# CHIP_PRO-Dev-Kit-v1_0.net
KiCad netlist of a schematic drawn in EAGLE
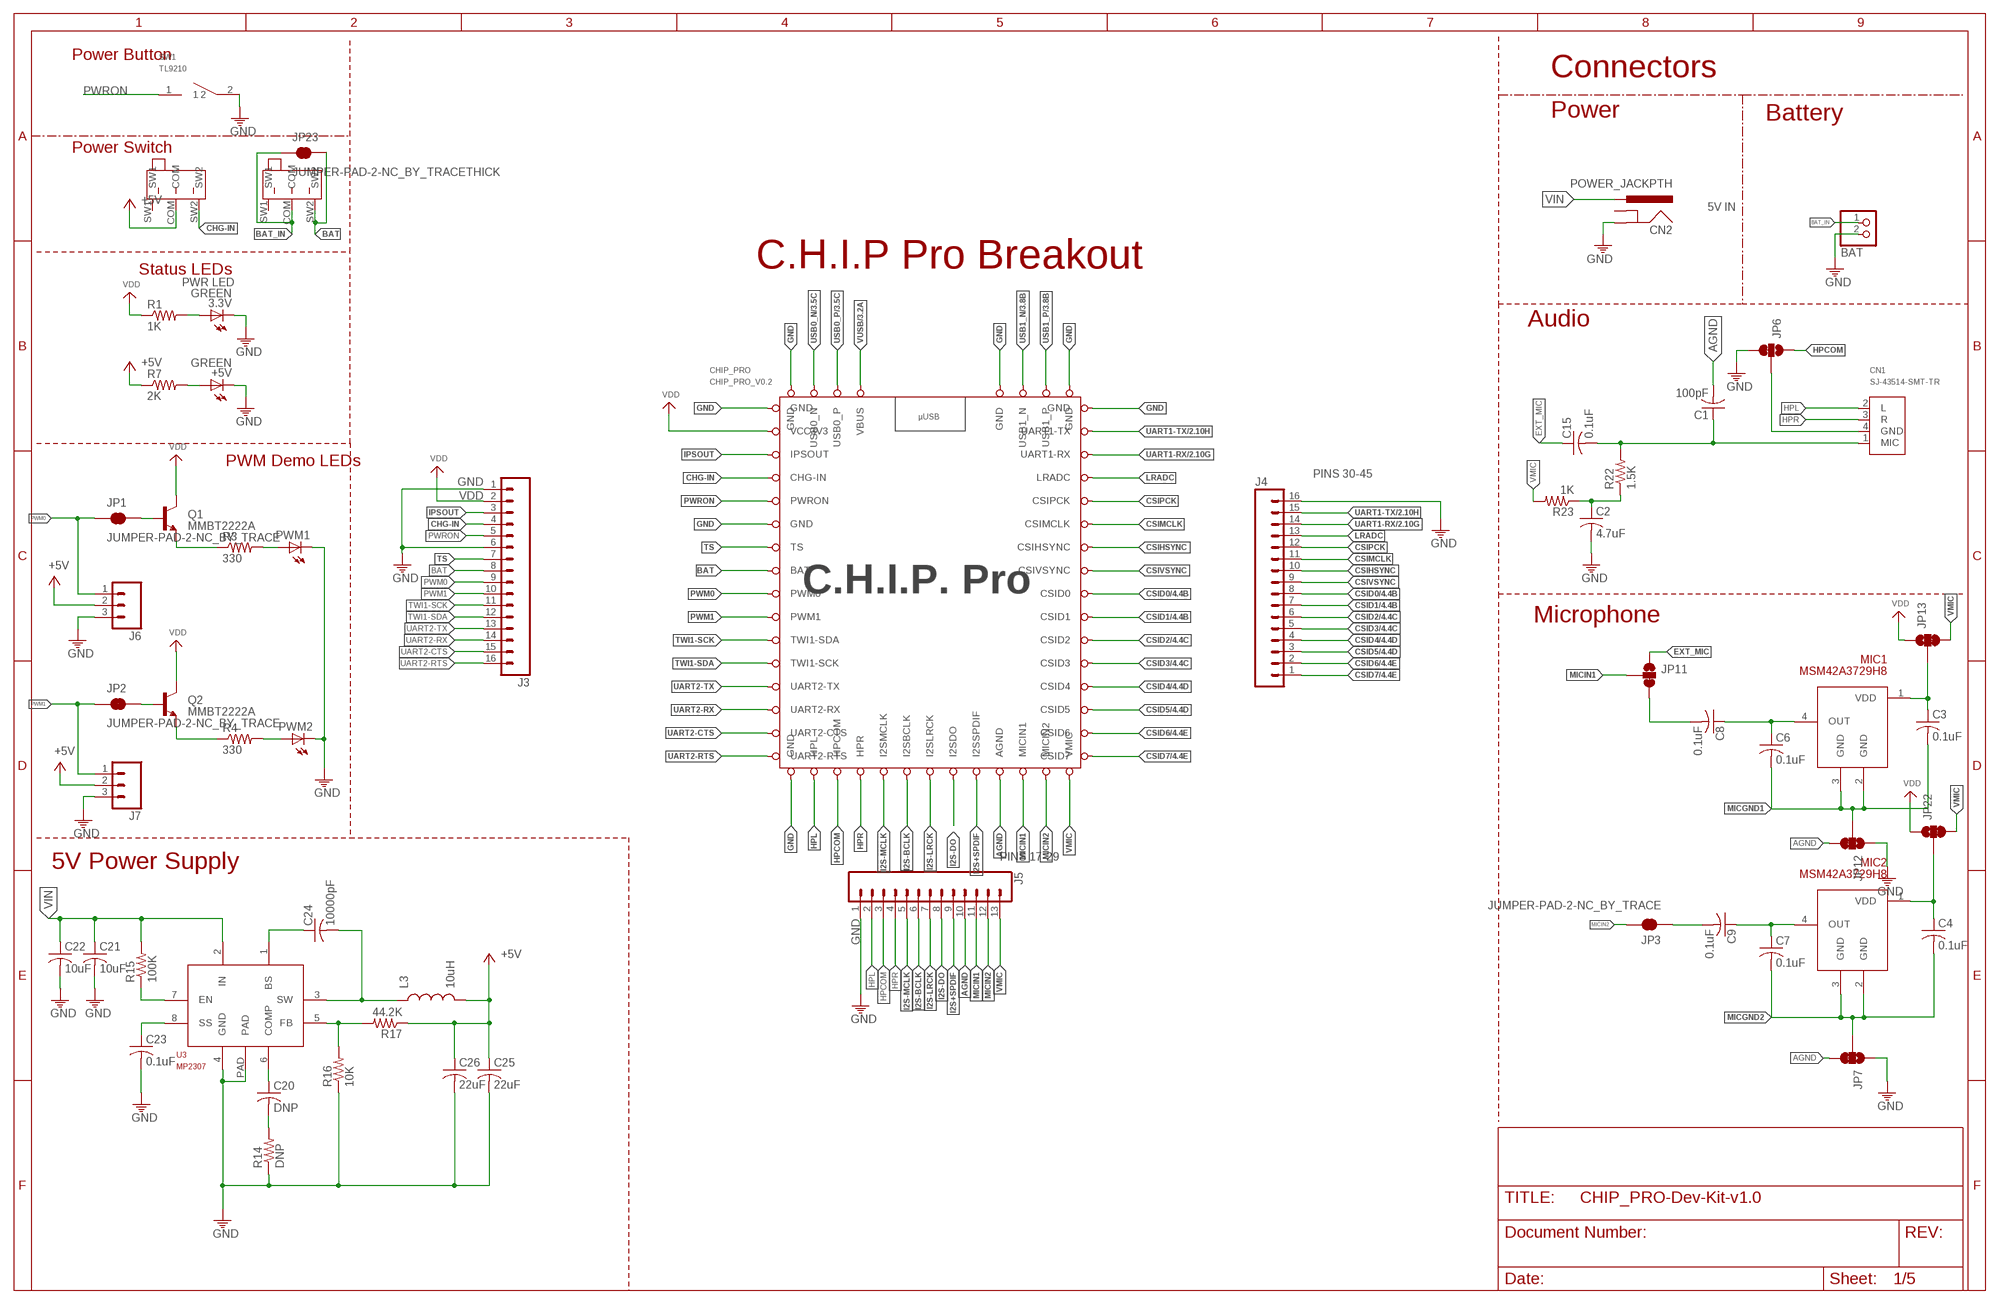
[diagram p0: schematic, sheet 1]
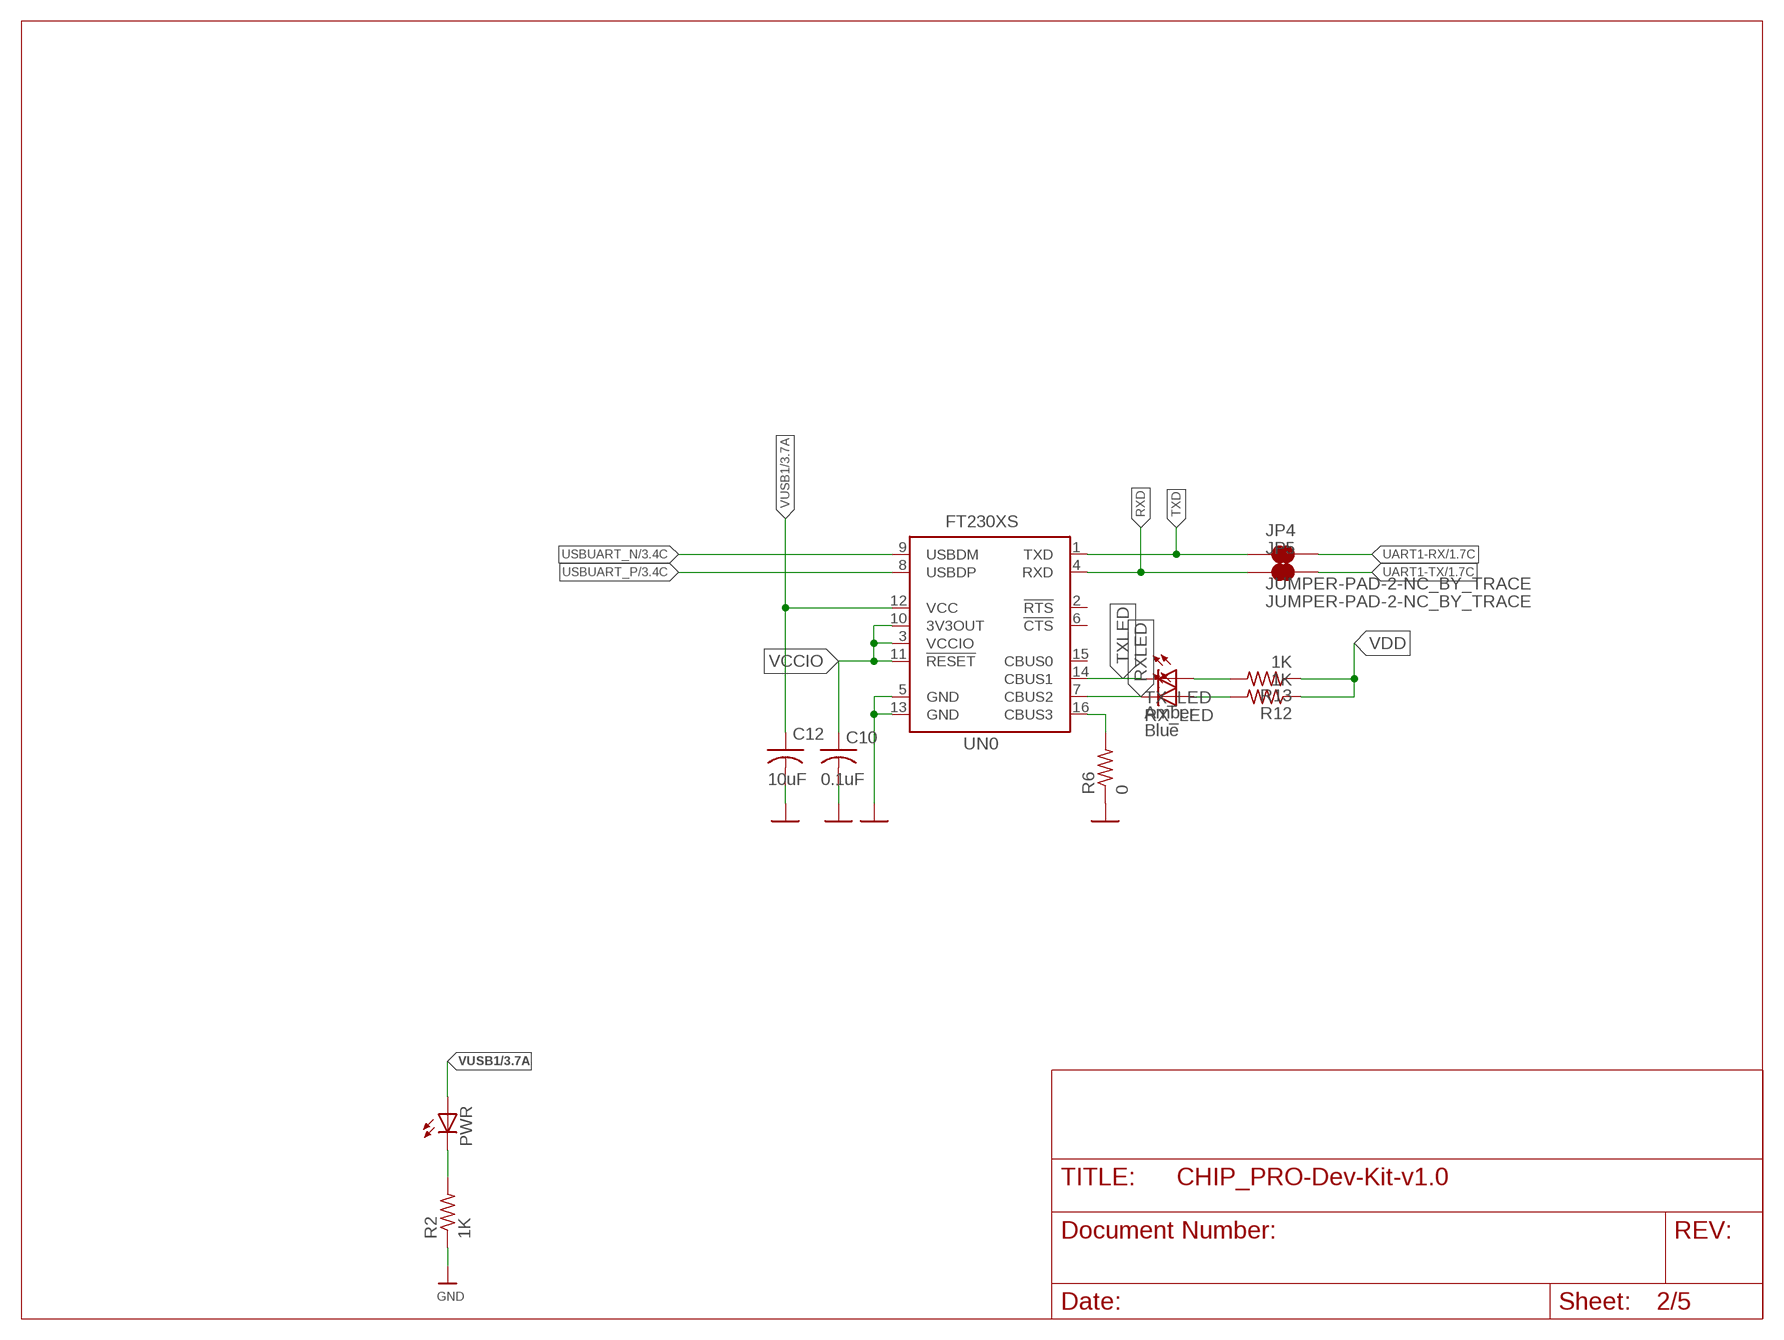
[diagram p1: schematic, sheet 2]
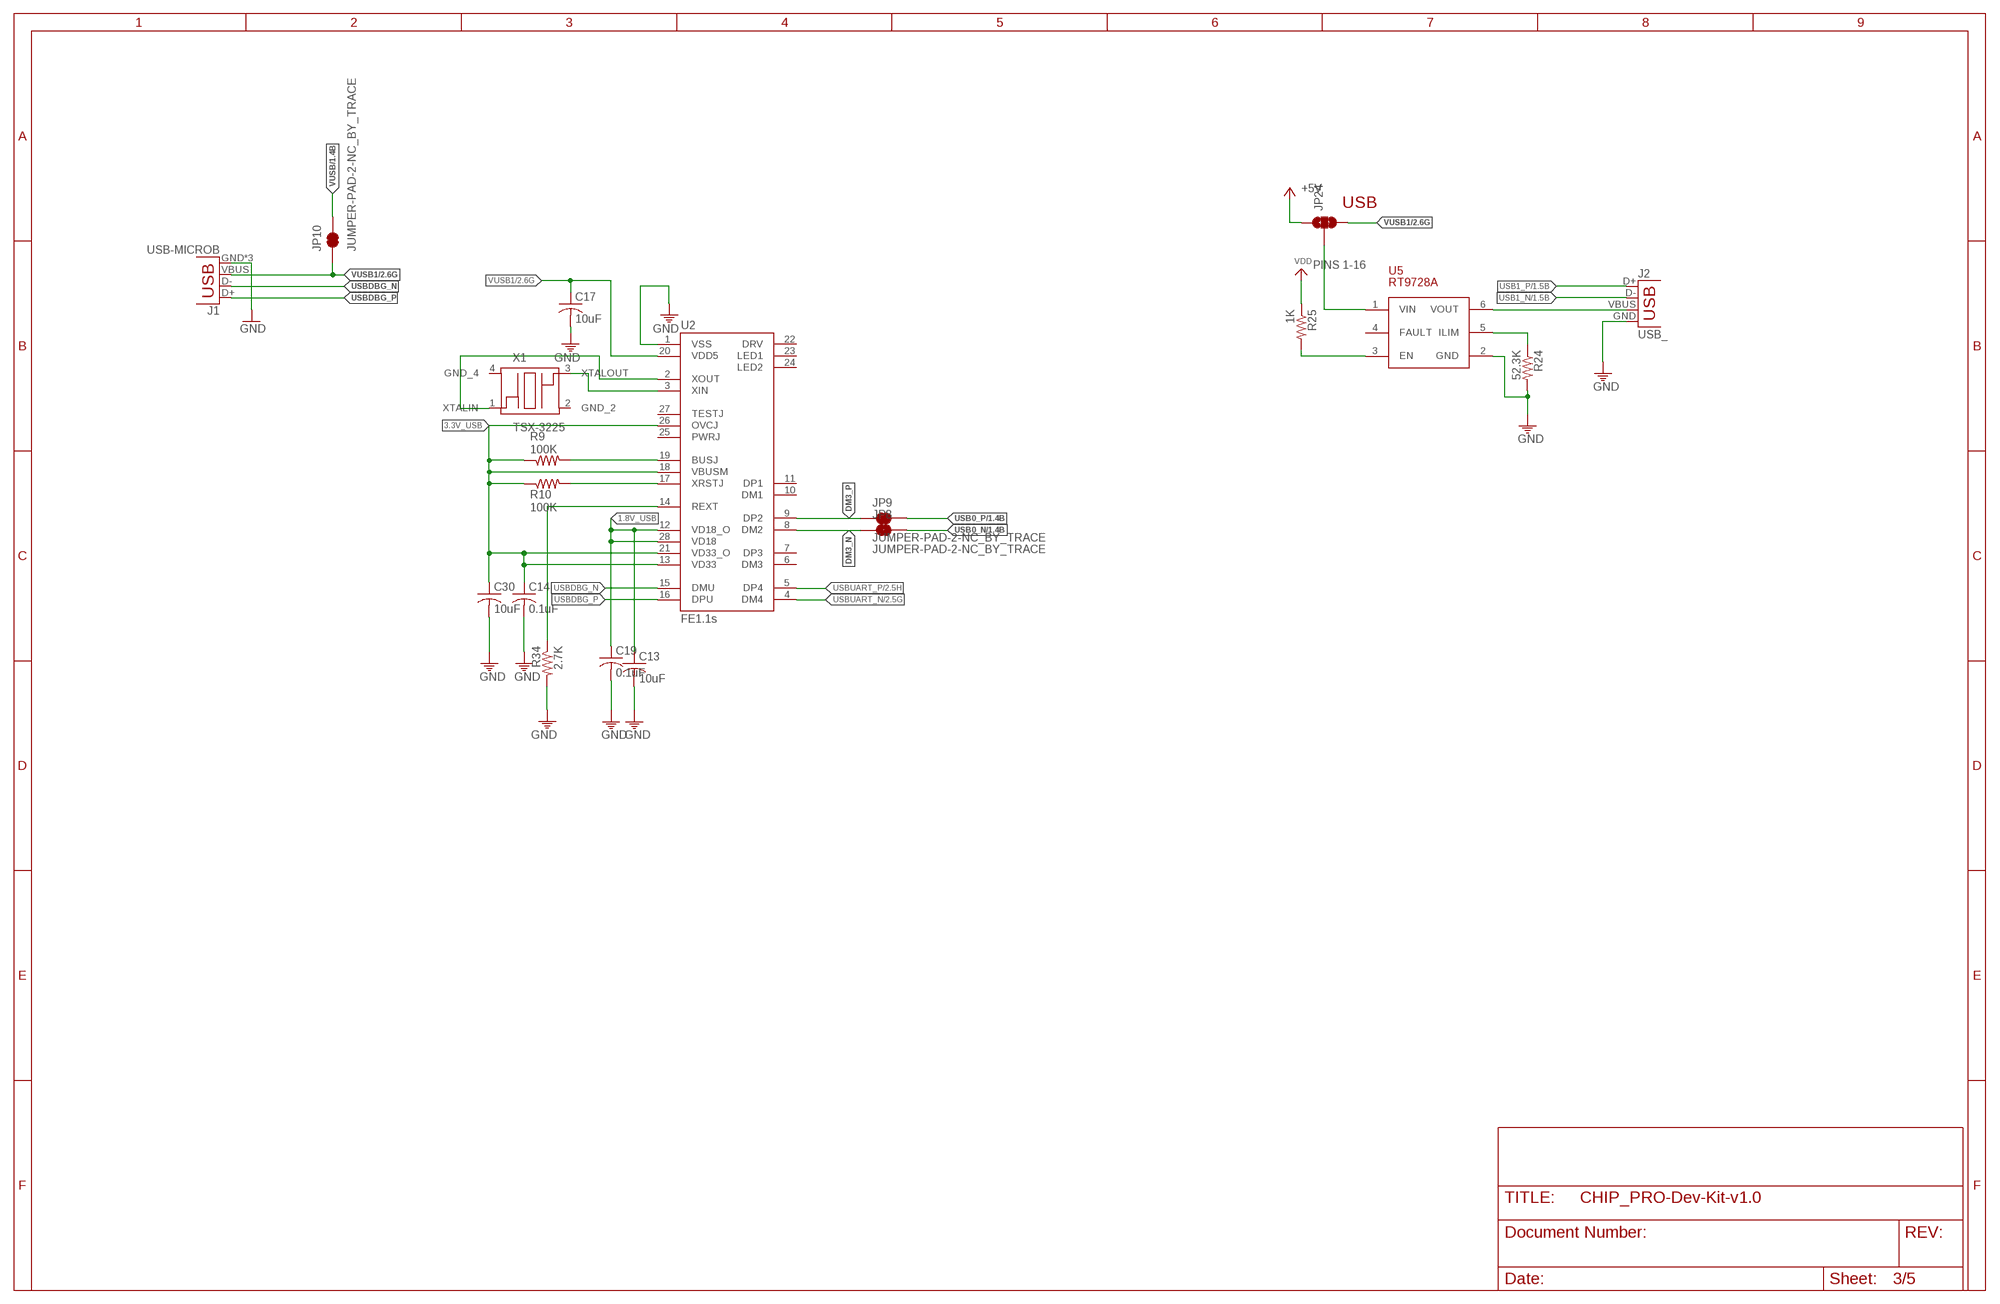
[diagram p2: schematic, sheet 3]
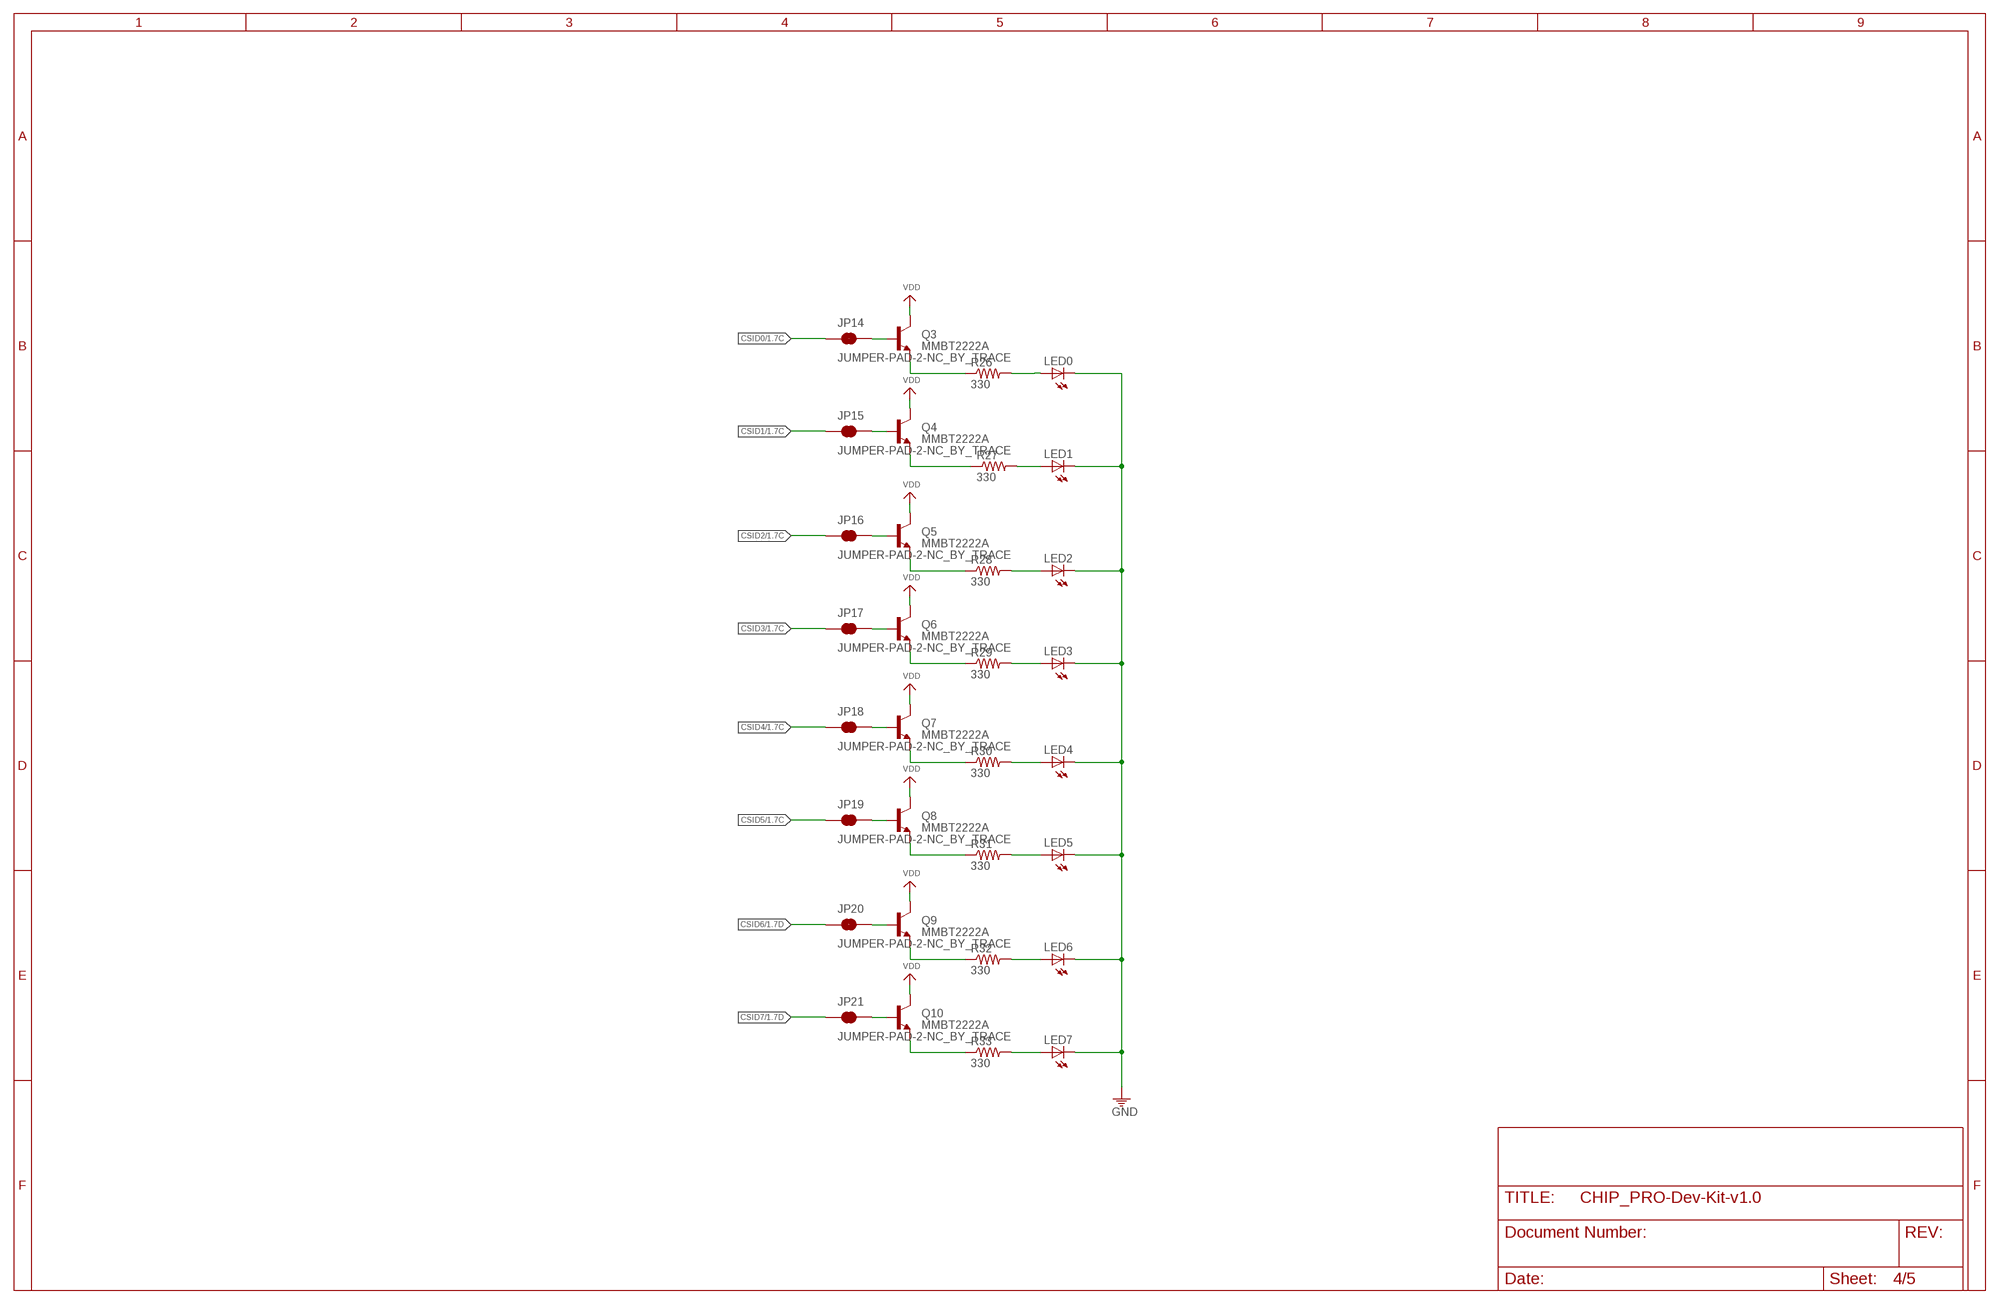
[diagram p3: schematic, sheet 4]

(export (version "E")
  (design (tool "Eeschema 10.0.6"))
  (components
    (comp (ref "C10")
      (value "0.1uF")
      (footprint "eagle-import:C0402")
      (libsource (lib "eagle-import") (part "C-USC0402"))
    )
    (comp (ref "C12")
      (value "10uF")
      (footprint "eagle-import:C0402")
      (libsource (lib "eagle-import") (part "C-USC0402"))
    )
    (comp (ref "JP4")
      (value "JUMPER-PAD-2-NC_BY_TRACE")
      (footprint "eagle-import:PAD-JUMPER-2-NC_BY_TRACE_YES_SILK")
      (libsource (lib "eagle-import") (part "JUMPER-PAD-2-NC_BY_TRACE"))
    )
    (comp (ref "JP5")
      (value "JUMPER-PAD-2-NC_BY_TRACE")
      (footprint "eagle-import:PAD-JUMPER-2-NC_BY_TRACE_YES_SILK")
      (libsource (lib "eagle-import") (part "JUMPER-PAD-2-NC_BY_TRACE"))
    )
    (comp (ref "PWR")
      (value "LED805")
      (footprint "eagle-import:LED-805")
      (libsource (lib "eagle-import") (part "LED805"))
    )
    (comp (ref "R2")
      (value "1K")
      (footprint "eagle-import:R0402")
      (libsource (lib "eagle-import") (part "GR8_Module-Eval-v0.1_R-US_R0402"))
    )
    (comp (ref "R6")
      (value "0")
      (footprint "eagle-import:R0402")
      (libsource (lib "eagle-import") (part "R-US_R0402"))
    )
    (comp (ref "R12")
      (value "1K")
      (footprint "eagle-import:R0402")
      (libsource (lib "eagle-import") (part "GR8_Module-Eval-v0.1_R-US_R0402"))
    )
    (comp (ref "R13")
      (value "1K")
      (footprint "eagle-import:R0402")
      (libsource (lib "eagle-import") (part "GR8_Module-Eval-v0.1_R-US_R0402"))
    )
    (comp (ref "RX_LED")
      (value "Blue")
      (footprint "eagle-import:LED-805")
      (libsource (lib "eagle-import") (part "LED805"))
    )
    (comp (ref "TX_LED")
      (value "Amber")
      (footprint "eagle-import:LED-805")
      (libsource (lib "eagle-import") (part "LED805"))
    )
    (comp (ref "UN0")
      (value "FT230XS")
      (footprint "eagle-import:SSOP-16")
      (libsource (lib "eagle-import") (part "FT230XS"))
    )
    (comp (ref "JP14")
      (value "JUMPER-PAD-2-NC_BY_TRACE")
      (footprint "eagle-import:PAD-JUMPER-2-NC_BY_TRACE_YES_SILK")
      (libsource (lib "eagle-import") (part "SparkFun-Passives_JUMPER-PAD-2-NC_BY_TRACE"))
    )
    (comp (ref "JP15")
      (value "JUMPER-PAD-2-NC_BY_TRACE")
      (footprint "eagle-import:PAD-JUMPER-2-NC_BY_TRACE_YES_SILK")
      (libsource (lib "eagle-import") (part "SparkFun-Passives_JUMPER-PAD-2-NC_BY_TRACE"))
    )
    (comp (ref "JP16")
      (value "JUMPER-PAD-2-NC_BY_TRACE")
      (footprint "eagle-import:PAD-JUMPER-2-NC_BY_TRACE_YES_SILK")
      (libsource (lib "eagle-import") (part "SparkFun-Passives_JUMPER-PAD-2-NC_BY_TRACE"))
    )
    (comp (ref "JP17")
      (value "JUMPER-PAD-2-NC_BY_TRACE")
      (footprint "eagle-import:PAD-JUMPER-2-NC_BY_TRACE_YES_SILK")
      (libsource (lib "eagle-import") (part "SparkFun-Passives_JUMPER-PAD-2-NC_BY_TRACE"))
    )
    (comp (ref "JP18")
      (value "JUMPER-PAD-2-NC_BY_TRACE")
      (footprint "eagle-import:PAD-JUMPER-2-NC_BY_TRACE_YES_SILK")
      (libsource (lib "eagle-import") (part "SparkFun-Passives_JUMPER-PAD-2-NC_BY_TRACE"))
    )
    (comp (ref "JP19")
      (value "JUMPER-PAD-2-NC_BY_TRACE")
      (footprint "eagle-import:PAD-JUMPER-2-NC_BY_TRACE_YES_SILK")
      (libsource (lib "eagle-import") (part "SparkFun-Passives_JUMPER-PAD-2-NC_BY_TRACE"))
    )
    (comp (ref "JP20")
      (value "JUMPER-PAD-2-NC_BY_TRACE")
      (footprint "eagle-import:PAD-JUMPER-2-NC_BY_TRACE_YES_SILK")
      (libsource (lib "eagle-import") (part "SparkFun-Passives_JUMPER-PAD-2-NC_BY_TRACE"))
    )
    (comp (ref "JP21")
      (value "JUMPER-PAD-2-NC_BY_TRACE")
      (footprint "eagle-import:PAD-JUMPER-2-NC_BY_TRACE_YES_SILK")
      (libsource (lib "eagle-import") (part "SparkFun-Passives_JUMPER-PAD-2-NC_BY_TRACE"))
    )
    (comp (ref "LED0")
      (value "LEDSMT1206")
      (footprint "eagle-import:1206")
      (libsource (lib "eagle-import") (part "LEDSMT1206"))
    )
    (comp (ref "LED1")
      (value "LEDSMT1206")
      (footprint "eagle-import:1206")
      (libsource (lib "eagle-import") (part "LEDSMT1206"))
    )
    (comp (ref "LED2")
      (value "LEDSMT1206")
      (footprint "eagle-import:1206")
      (libsource (lib "eagle-import") (part "LEDSMT1206"))
    )
    (comp (ref "LED3")
      (value "LEDSMT1206")
      (footprint "eagle-import:1206")
      (libsource (lib "eagle-import") (part "LEDSMT1206"))
    )
    (comp (ref "LED4")
      (value "LEDSMT1206")
      (footprint "eagle-import:1206")
      (libsource (lib "eagle-import") (part "LEDSMT1206"))
    )
    (comp (ref "LED5")
      (value "LEDSMT1206")
      (footprint "eagle-import:1206")
      (libsource (lib "eagle-import") (part "LEDSMT1206"))
    )
    (comp (ref "LED6")
      (value "LEDSMT1206")
      (footprint "eagle-import:1206")
      (libsource (lib "eagle-import") (part "LEDSMT1206"))
    )
    (comp (ref "LED7")
      (value "LEDSMT1206")
      (footprint "eagle-import:1206")
      (libsource (lib "eagle-import") (part "LEDSMT1206"))
    )
    (comp (ref "Q3")
      (value "MMBT2222A")
      (footprint "eagle-import:SOT23-3")
      (libsource (lib "eagle-import") (part "TRANSISTOR_NPNMMBT2222A"))
    )
    (comp (ref "Q4")
      (value "MMBT2222A")
      (footprint "eagle-import:SOT23-3")
      (libsource (lib "eagle-import") (part "TRANSISTOR_NPNMMBT2222A"))
    )
    (comp (ref "Q5")
      (value "MMBT2222A")
      (footprint "eagle-import:SOT23-3")
      (libsource (lib "eagle-import") (part "TRANSISTOR_NPNMMBT2222A"))
    )
    (comp (ref "Q6")
      (value "MMBT2222A")
      (footprint "eagle-import:SOT23-3")
      (libsource (lib "eagle-import") (part "TRANSISTOR_NPNMMBT2222A"))
    )
    (comp (ref "Q7")
      (value "MMBT2222A")
      (footprint "eagle-import:SOT23-3")
      (libsource (lib "eagle-import") (part "TRANSISTOR_NPNMMBT2222A"))
    )
    (comp (ref "Q8")
      (value "MMBT2222A")
      (footprint "eagle-import:SOT23-3")
      (libsource (lib "eagle-import") (part "TRANSISTOR_NPNMMBT2222A"))
    )
    (comp (ref "Q9")
      (value "MMBT2222A")
      (footprint "eagle-import:SOT23-3")
      (libsource (lib "eagle-import") (part "TRANSISTOR_NPNMMBT2222A"))
    )
    (comp (ref "Q10")
      (value "MMBT2222A")
      (footprint "eagle-import:SOT23-3")
      (libsource (lib "eagle-import") (part "TRANSISTOR_NPNMMBT2222A"))
    )
    (comp (ref "R26")
      (value "330")
      (footprint "eagle-import:R0603")
      (libsource (lib "eagle-import") (part "adafruit_R-US_R0603"))
    )
    (comp (ref "R27")
      (value "330")
      (footprint "eagle-import:R0603")
      (libsource (lib "eagle-import") (part "adafruit_R-US_R0603"))
    )
    (comp (ref "R28")
      (value "330")
      (footprint "eagle-import:R0603")
      (libsource (lib "eagle-import") (part "adafruit_R-US_R0603"))
    )
    (comp (ref "R29")
      (value "330")
      (footprint "eagle-import:R0603")
      (libsource (lib "eagle-import") (part "adafruit_R-US_R0603"))
    )
    (comp (ref "R30")
      (value "330")
      (footprint "eagle-import:R0603")
      (libsource (lib "eagle-import") (part "adafruit_R-US_R0603"))
    )
    (comp (ref "R31")
      (value "330")
      (footprint "eagle-import:R0603")
      (libsource (lib "eagle-import") (part "adafruit_R-US_R0603"))
    )
    (comp (ref "R32")
      (value "330")
      (footprint "eagle-import:R0603")
      (libsource (lib "eagle-import") (part "adafruit_R-US_R0603"))
    )
    (comp (ref "R33")
      (value "330")
      (footprint "eagle-import:R0603")
      (libsource (lib "eagle-import") (part "adafruit_R-US_R0603"))
    )
    (comp (ref "+5V")
      (value "GREEN")
      (footprint "eagle-import:1206")
      (libsource (lib "eagle-import") (part "LEDSMT1206"))
    )
    (comp (ref "3.3V")
      (value "GREEN")
      (footprint "eagle-import:1206")
      (libsource (lib "eagle-import") (part "LEDSMT1206"))
    )
    (comp (ref "BAT")
      (value "JST_2PIN-SMT-RA")
      (footprint "eagle-import:JST-PH-2-SMT-RA")
      (libsource (lib "eagle-import") (part "JST_2PIN-SMT-RA"))
    )
    (comp (ref "C1")
      (value "100pF")
      (footprint "eagle-import:C0402")
      (libsource (lib "eagle-import") (part "resistor_C-USC0402"))
    )
    (comp (ref "C2")
      (value "4.7uF")
      (footprint "eagle-import:C0402")
      (libsource (lib "eagle-import") (part "resistor_C-USC0402"))
    )
    (comp (ref "C3")
      (value "0.1uF")
      (footprint "eagle-import:C0402")
      (libsource (lib "eagle-import") (part "resistor_C-USC0402"))
    )
    (comp (ref "C4")
      (value "0.1uF")
      (footprint "eagle-import:C0402")
      (libsource (lib "eagle-import") (part "resistor_C-USC0402"))
    )
    (comp (ref "C6")
      (value "0.1uF")
      (footprint "eagle-import:C0402")
      (libsource (lib "eagle-import") (part "resistor_C-USC0402"))
    )
    (comp (ref "C7")
      (value "0.1uF")
      (footprint "eagle-import:C0402")
      (libsource (lib "eagle-import") (part "resistor_C-USC0402"))
    )
    (comp (ref "C8")
      (value "0.1uF")
      (footprint "eagle-import:C0402")
      (libsource (lib "eagle-import") (part "resistor_C-USC0402"))
    )
    (comp (ref "C9")
      (value "0.1uF")
      (footprint "eagle-import:C0402")
      (libsource (lib "eagle-import") (part "resistor_C-USC0402"))
    )
    (comp (ref "C15")
      (value "0.1uF")
      (footprint "eagle-import:C0402")
      (libsource (lib "eagle-import") (part "resistor_C-USC0402"))
    )
    (comp (ref "C20")
      (value "DNP")
      (footprint "eagle-import:C0402")
      (libsource (lib "eagle-import") (part "GR8_Module-Eval-v0.1_C-USC0402"))
    )
    (comp (ref "C21")
      (value "10uF")
      (footprint "eagle-import:C0603")
      (libsource (lib "eagle-import") (part "GR8_Module-Eval-v0.1_C-USC0603"))
    )
    (comp (ref "C22")
      (value "10uF")
      (footprint "eagle-import:C0603")
      (libsource (lib "eagle-import") (part "GR8_Module-Eval-v0.1_C-USC0603"))
    )
    (comp (ref "C23")
      (value "0.1uF")
      (footprint "eagle-import:C0402")
      (libsource (lib "eagle-import") (part "GR8_Module-Eval-v0.1_C-USC0402"))
    )
    (comp (ref "C24")
      (value "10000pF")
      (footprint "eagle-import:C0603")
      (libsource (lib "eagle-import") (part "C-USC0603"))
    )
    (comp (ref "C25")
      (value "22uF")
      (footprint "eagle-import:C0805")
      (libsource (lib "eagle-import") (part "C-USC0805"))
    )
    (comp (ref "C26")
      (value "22uF")
      (footprint "eagle-import:C0805")
      (libsource (lib "eagle-import") (part "C-USC0805"))
    )
    (comp (ref "CHIP_PRO")
      (value "CHIP_PRO_V0.2")
      (footprint "eagle-import:GR8_MODULE_V0.2")
      (libsource (lib "eagle-import") (part "GR8_MODULE_V0.1"))
    )
    (comp (ref "CN1")
      (value "SJ-43514-SMT-TR")
      (footprint "eagle-import:SJ-43514-SMT-TR")
      (libsource (lib "eagle-import") (part "SJ-43514-SMT-TR"))
    )
    (comp (ref "CN2")
      (value "POWER_JACKPTH")
      (footprint "eagle-import:POWER_JACK_PTH")
      (libsource (lib "eagle-import") (part "POWER_JACKPTH"))
    )
    (comp (ref "J3")
      (value "M16LOCK_LONGPADS")
      (footprint "eagle-import:1X16_LOCK_LONGPADS")
      (libsource (lib "eagle-import") (part "M16LOCK_LONGPADS"))
    )
    (comp (ref "J4")
      (value "M16LOCK_LONGPADS")
      (footprint "eagle-import:1X16_LOCK_LONGPADS")
      (libsource (lib "eagle-import") (part "M16LOCK_LONGPADS"))
    )
    (comp (ref "J5")
      (value "M13LOCK")
      (footprint "eagle-import:1X13_LOCK")
      (libsource (lib "eagle-import") (part "M13LOCK"))
    )
    (comp (ref "J6")
      (value "M03LOCK")
      (footprint "eagle-import:1X03_LOCK")
      (libsource (lib "eagle-import") (part "M03LOCK"))
    )
    (comp (ref "J7")
      (value "M03LOCK")
      (footprint "eagle-import:1X03_LOCK")
      (libsource (lib "eagle-import") (part "M03LOCK"))
    )
    (comp (ref "JP1")
      (value "JUMPER-PAD-2-NC_BY_TRACE")
      (footprint "eagle-import:PAD-JUMPER-2-NC_BY_TRACE_YES_SILK")
      (libsource (lib "eagle-import") (part "JUMPER-PAD-2-NC_BY_TRACE"))
    )
    (comp (ref "JP2")
      (value "JUMPER-PAD-2-NC_BY_TRACE")
      (footprint "eagle-import:PAD-JUMPER-2-NC_BY_TRACE_YES_SILK")
      (libsource (lib "eagle-import") (part "JUMPER-PAD-2-NC_BY_TRACE"))
    )
    (comp (ref "JP3")
      (value "JUMPER-PAD-2-NC_BY_TRACE")
      (footprint "eagle-import:PAD-JUMPER-2-NC_BY_TRACE_YES_SILK")
      (libsource (lib "eagle-import") (part "JUMPER-PAD-2-NC_BY_TRACE"))
    )
    (comp (ref "JP6")
      (value "JUMPER-PAD-3-2OF3_NC_BY_TRACE_LARGE")
      (footprint "eagle-import:PAD-JUMPER-3-2OF3_NC_BY_TRACE_YES_SILK_LARGE")
      (libsource (lib "eagle-import") (part "JUMPER-PAD-3-2OF3_NC_BY_TRACE_LARGE"))
    )
    (comp (ref "JP7")
      (value "JUMPER-PAD-3-2OF3_NC_BY_TRACE_LARGE")
      (footprint "eagle-import:PAD-JUMPER-3-2OF3_NC_BY_TRACE_YES_SILK_LARGE")
      (libsource (lib "eagle-import") (part "JUMPER-PAD-3-2OF3_NC_BY_TRACE_LARGE"))
    )
    (comp (ref "JP11")
      (value "JUMPER-PAD-3-2OF3_NC_BY_TRACE_LARGE")
      (footprint "eagle-import:PAD-JUMPER-3-2OF3_NC_BY_TRACE_YES_SILK_LARGE")
      (libsource (lib "eagle-import") (part "JUMPER-PAD-3-2OF3_NC_BY_TRACE_LARGE"))
    )
    (comp (ref "JP12")
      (value "JUMPER-PAD-3-2OF3_NC_BY_TRACE_LARGE")
      (footprint "eagle-import:PAD-JUMPER-3-2OF3_NC_BY_TRACE_YES_SILK_LARGE")
      (libsource (lib "eagle-import") (part "JUMPER-PAD-3-2OF3_NC_BY_TRACE_LARGE"))
    )
    (comp (ref "JP13")
      (value "JUMPER-PAD-3-2OF3_NC_BY_TRACE_LARGE")
      (footprint "eagle-import:PAD-JUMPER-3-2OF3_NC_BY_TRACE_YES_SILK_LARGE")
      (libsource (lib "eagle-import") (part "JUMPER-PAD-3-2OF3_NC_BY_TRACE_LARGE"))
    )
    (comp (ref "JP22")
      (value "JUMPER-PAD-3-2OF3_NC_BY_TRACE_LARGE")
      (footprint "eagle-import:PAD-JUMPER-3-2OF3_NC_BY_TRACE_YES_SILK_LARGE")
      (libsource (lib "eagle-import") (part "JUMPER-PAD-3-2OF3_NC_BY_TRACE_LARGE"))
    )
    (comp (ref "JP23")
      (value "JUMPER-PAD-2-NC_BY_TRACETHICK")
      (footprint "eagle-import:PAD-JUMPER-2-NC_BY_TRACE_YES_SILK_THICK")
      (libsource (lib "eagle-import") (part "JUMPER-PAD-2-NC_BY_TRACETHICK"))
    )
    (comp (ref "L3")
      (value "10uH")
      (footprint "eagle-import:INDUCTOR_NR8040")
      (libsource (lib "eagle-import") (part "INDUCTORNR8040"))
    )
    (comp (ref "MIC1")
      (value "MSM42A3729H8")
      (footprint "eagle-import:MSM42A3729H8")
      (libsource (lib "eagle-import") (part "MSM42A3729H8"))
    )
    (comp (ref "MIC2")
      (value "MSM42A3729H8")
      (footprint "eagle-import:MSM42A3729H8")
      (libsource (lib "eagle-import") (part "MSM42A3729H8"))
    )
    (comp (ref "PWM1")
      (value "LEDSMT1206")
      (footprint "eagle-import:1206")
      (libsource (lib "eagle-import") (part "LEDSMT1206"))
    )
    (comp (ref "PWM2")
      (value "LEDSMT1206")
      (footprint "eagle-import:1206")
      (libsource (lib "eagle-import") (part "LEDSMT1206"))
    )
    (comp (ref "Q1")
      (value "MMBT2222A")
      (footprint "eagle-import:SOT23-3")
      (libsource (lib "eagle-import") (part "TRANSISTOR_NPNMMBT2222A"))
    )
    (comp (ref "Q2")
      (value "MMBT2222A")
      (footprint "eagle-import:SOT23-3")
      (libsource (lib "eagle-import") (part "TRANSISTOR_NPNMMBT2222A"))
    )
    (comp (ref "R1")
      (value "1K")
      (footprint "eagle-import:R0603")
      (libsource (lib "eagle-import") (part "adafruit_R-US_R0603"))
    )
    (comp (ref "R3")
      (value "330")
      (footprint "eagle-import:R0603")
      (libsource (lib "eagle-import") (part "adafruit_R-US_R0603"))
    )
    (comp (ref "R4")
      (value "330")
      (footprint "eagle-import:R0603")
      (libsource (lib "eagle-import") (part "adafruit_R-US_R0603"))
    )
    (comp (ref "R7")
      (value "2K")
      (footprint "eagle-import:R0603")
      (libsource (lib "eagle-import") (part "adafruit_R-US_R0603"))
    )
    (comp (ref "R14")
      (value "DNP")
      (footprint "eagle-import:R0402")
      (libsource (lib "eagle-import") (part "GR8_Module-Eval-v0.1_R-US_R0402"))
    )
    (comp (ref "R15")
      (value "100K")
      (footprint "eagle-import:R0402")
      (libsource (lib "eagle-import") (part "GR8_Module-Eval-v0.1_R-US_R0402"))
    )
    (comp (ref "R16")
      (value "10K")
      (footprint "eagle-import:R0402")
      (libsource (lib "eagle-import") (part "GR8_Module-Eval-v0.1_R-US_R0402"))
    )
    (comp (ref "R17")
      (value "44.2K")
      (footprint "eagle-import:R0402")
      (libsource (lib "eagle-import") (part "GR8_Module-Eval-v0.1_R-US_R0402"))
    )
    (comp (ref "R22")
      (value "1.5K")
      (footprint "eagle-import:R0402")
      (libsource (lib "eagle-import") (part "resistor_R-US_R0402"))
    )
    (comp (ref "R23")
      (value "1K")
      (footprint "eagle-import:R0402")
      (libsource (lib "eagle-import") (part "resistor_R-US_R0402"))
    )
    (comp (ref "SW1")
      (value "TL9210")
      (footprint "eagle-import:TL9210_SW")
      (libsource (lib "eagle-import") (part "TL9210"))
    )
    (comp (ref "SW2")
      (value "SLIDE_SWITCHESYSS-19-1202-N")
      (footprint "eagle-import:YSS-19-1202-N")
      (libsource (lib "eagle-import") (part "SLIDE_SWITCHESYSS-19-1202-N"))
    )
    (comp (ref "SW3")
      (value "SLIDE_SWITCHESYSS-19-1202-N")
      (footprint "eagle-import:YSS-19-1202-N")
      (libsource (lib "eagle-import") (part "SLIDE_SWITCHESYSS-19-1202-N"))
    )
    (comp (ref "U3")
      (value "MP2307")
      (footprint "eagle-import:SOIC-8-PAD")
      (libsource (lib "eagle-import") (part "MP2307"))
    )
    (comp (ref "C13")
      (value "10uF")
      (footprint "eagle-import:C0603")
      (libsource (lib "eagle-import") (part "GR8_Module-Eval-v0.2_C-USC0603"))
    )
    (comp (ref "C14")
      (value "0.1uF")
      (footprint "eagle-import:C0402")
      (libsource (lib "eagle-import") (part "GR8_Module-Eval-v0.2_C-USC0402"))
    )
    (comp (ref "C17")
      (value "10uF")
      (footprint "eagle-import:C0603")
      (libsource (lib "eagle-import") (part "GR8_Module-Eval-v0.2_C-USC0603"))
    )
    (comp (ref "C19")
      (value "0.1uF")
      (footprint "eagle-import:C0402")
      (libsource (lib "eagle-import") (part "GR8_Module-Eval-v0.2_C-USC0402"))
    )
    (comp (ref "C30")
      (value "10uF")
      (footprint "eagle-import:C0603")
      (libsource (lib "eagle-import") (part "GR8_Module-Eval-v0.2_C-USC0603"))
    )
    (comp (ref "J1")
      (value "USB-MICROB")
      (footprint "eagle-import:USB-MICROB")
      (libsource (lib "eagle-import") (part "USB-MICROB"))
    )
    (comp (ref "J2")
      (value "USB_")
      (footprint "eagle-import:USB-A-S-SILK-FEMALE")
      (libsource (lib "eagle-import") (part "USB_"))
    )
    (comp (ref "JP8")
      (value "JUMPER-PAD-2-NC_BY_TRACE")
      (footprint "eagle-import:PAD-JUMPER-2-NC_BY_TRACE_YES_SILK")
      (libsource (lib "eagle-import") (part "JUMPER-PAD-2-NC_BY_TRACE"))
    )
    (comp (ref "JP9")
      (value "JUMPER-PAD-2-NC_BY_TRACE")
      (footprint "eagle-import:PAD-JUMPER-2-NC_BY_TRACE_YES_SILK")
      (libsource (lib "eagle-import") (part "JUMPER-PAD-2-NC_BY_TRACE"))
    )
    (comp (ref "JP10")
      (value "JUMPER-PAD-2-NC_BY_TRACE")
      (footprint "eagle-import:PAD-JUMPER-2-NC_BY_TRACE_YES_SILK")
      (libsource (lib "eagle-import") (part "JUMPER-PAD-2-NC_BY_TRACE"))
    )
    (comp (ref "JP24")
      (value "JUMPER-PAD-3-2OF3_NC_BY_TRACE_LARGE")
      (footprint "eagle-import:PAD-JUMPER-3-2OF3_NC_BY_TRACE_YES_SILK_LARGE")
      (libsource (lib "eagle-import") (part "JUMPER-PAD-3-2OF3_NC_BY_TRACE_LARGE"))
    )
    (comp (ref "R9")
      (value "100K")
      (footprint "eagle-import:R0402")
      (libsource (lib "eagle-import") (part "resistor_R-US_R0402"))
    )
    (comp (ref "R10")
      (value "100K")
      (footprint "eagle-import:R0402")
      (libsource (lib "eagle-import") (part "resistor_R-US_R0402"))
    )
    (comp (ref "R24")
      (value "52.3K")
      (footprint "eagle-import:R0402")
      (libsource (lib "eagle-import") (part "resistor_R-US_R0402"))
    )
    (comp (ref "R25")
      (value "1K")
      (footprint "eagle-import:R0402")
      (libsource (lib "eagle-import") (part "resistor_R-US_R0402"))
    )
    (comp (ref "R34")
      (value "2.7K")
      (footprint "eagle-import:R0402")
      (libsource (lib "eagle-import") (part "resistor_R-US_R0402"))
    )
    (comp (ref "U2")
      (value "FE1.1S")
      (footprint "eagle-import:FE1.1S_SSOP-28")
      (libsource (lib "eagle-import") (part "FE1.1S"))
    )
    (comp (ref "U5")
      (value "RT9728A")
      (footprint "eagle-import:SOT-23-6")
      (libsource (lib "eagle-import") (part "RT9728A"))
    )
    (comp (ref "X1")
      (value "TSX-3225")
      (footprint "eagle-import:TSX-3225")
      (libsource (lib "eagle-import") (part "TSX-3225"))
    )
  )
  (nets
    (net (code "1") (name "+5V") (class "Default")
      (node (ref "C25") (pin "1") (pinfunction "1_1") (pintype "passive"))
      (node (ref "C26") (pin "1") (pinfunction "1_1") (pintype "passive"))
      (node (ref "J6") (pin "2") (pinfunction "2_2") (pintype "passive"))
      (node (ref "J7") (pin "2") (pinfunction "2_2") (pintype "passive"))
      (node (ref "JP24") (pin "1") (pinfunction "1_1") (pintype "passive"))
      (node (ref "L3") (pin "P$2") (pinfunction "2_P$2") (pintype "passive"))
      (node (ref "R17") (pin "1") (pinfunction "1_1") (pintype "passive"))
      (node (ref "R7") (pin "1") (pinfunction "1_1") (pintype "passive"))
      (node (ref "SW2") (pin "COM") (pinfunction "COM_COM") (pintype "bidirectional"))
    )
    (net (code "2") (name "1.8V_USB") (class "Default")
      (node (ref "C13") (pin "1") (pinfunction "1_1") (pintype "passive"))
      (node (ref "C19") (pin "1") (pinfunction "1_1") (pintype "passive"))
      (node (ref "U2") (pin "12") (pinfunction "VD18_O_12") (pintype "bidirectional"))
      (node (ref "U2") (pin "28") (pinfunction "VD18_28") (pintype "bidirectional"))
    )
    (net (code "3") (name "3.3V_USB") (class "Default")
      (node (ref "C14") (pin "1") (pinfunction "1_1") (pintype "passive"))
      (node (ref "C30") (pin "1") (pinfunction "1_1") (pintype "passive"))
      (node (ref "R10") (pin "1") (pinfunction "1_1") (pintype "passive"))
      (node (ref "R9") (pin "1") (pinfunction "1_1") (pintype "passive"))
      (node (ref "U2") (pin "13") (pinfunction "VD33_13") (pintype "bidirectional"))
      (node (ref "U2") (pin "18") (pinfunction "VBUSM_18") (pintype "bidirectional"))
      (node (ref "U2") (pin "21") (pinfunction "VD33_O_21") (pintype "bidirectional"))
      (node (ref "U2") (pin "26") (pinfunction "OVCJ_26") (pintype "bidirectional"))
    )
    (net (code "4") (name "AGND") (class "Default")
      (node (ref "C1") (pin "2") (pinfunction "2_2") (pintype "passive"))
      (node (ref "CHIP_PRO") (pin "AGND") (pinfunction "AGND_AGND") (pintype "power_in"))
      (node (ref "J5") (pin "10") (pinfunction "10_10") (pintype "passive"))
      (node (ref "JP12") (pin "3") (pinfunction "3_3") (pintype "passive"))
      (node (ref "JP7") (pin "3") (pinfunction "3_3") (pintype "passive"))
    )
    (net (code "5") (name "BAT") (class "Default")
      (node (ref "CHIP_PRO") (pin "BAT") (pinfunction "BAT_BAT") (pintype "bidirectional"))
      (node (ref "J3") (pin "8") (pinfunction "8_8") (pintype "passive"))
      (node (ref "JP23") (pin "2") (pinfunction "2_2") (pintype "passive"))
      (node (ref "SW3") (pin "SW2") (pinfunction "SW2_SW2") (pintype "bidirectional"))
    )
    (net (code "6") (name "BAT_IN") (class "Default")
      (node (ref "BAT") (pin "1") (pinfunction "2_1") (pintype "passive"))
      (node (ref "JP23") (pin "1") (pinfunction "1_1") (pintype "passive"))
      (node (ref "SW3") (pin "COM") (pinfunction "COM_COM") (pintype "bidirectional"))
    )
    (net (code "7") (name "CHG-IN") (class "Default")
      (node (ref "CHIP_PRO") (pin "CHG-IN") (pinfunction "CHG-IN_CHG-IN") (pintype "power_in"))
      (node (ref "J3") (pin "4") (pinfunction "4_4") (pintype "passive"))
      (node (ref "SW2") (pin "SW2") (pinfunction "SW2_SW2") (pintype "bidirectional"))
    )
    (net (code "8") (name "CSID0") (class "Default")
      (node (ref "CHIP_PRO") (pin "CSID0") (pinfunction "CSID0_CSID0") (pintype "bidirectional"))
      (node (ref "J4") (pin "8") (pinfunction "8_8") (pintype "passive"))
      (node (ref "JP14") (pin "1") (pinfunction "1_1") (pintype "passive"))
    )
    (net (code "9") (name "CSID1") (class "Default")
      (node (ref "CHIP_PRO") (pin "CSID1") (pinfunction "CSID1_CSID1") (pintype "bidirectional"))
      (node (ref "J4") (pin "7") (pinfunction "7_7") (pintype "passive"))
      (node (ref "JP15") (pin "1") (pinfunction "1_1") (pintype "passive"))
    )
    (net (code "10") (name "CSID2") (class "Default")
      (node (ref "CHIP_PRO") (pin "CSID2") (pinfunction "CSID2_CSID2") (pintype "bidirectional"))
      (node (ref "J4") (pin "6") (pinfunction "6_6") (pintype "passive"))
      (node (ref "JP16") (pin "1") (pinfunction "1_1") (pintype "passive"))
    )
    (net (code "11") (name "CSID3") (class "Default")
      (node (ref "CHIP_PRO") (pin "CSID3") (pinfunction "CSID3_CSID3") (pintype "bidirectional"))
      (node (ref "J4") (pin "5") (pinfunction "5_5") (pintype "passive"))
      (node (ref "JP17") (pin "1") (pinfunction "1_1") (pintype "passive"))
    )
    (net (code "12") (name "CSID4") (class "Default")
      (node (ref "CHIP_PRO") (pin "CSID4") (pinfunction "CSID4_CSID4") (pintype "bidirectional"))
      (node (ref "J4") (pin "4") (pinfunction "4_4") (pintype "passive"))
      (node (ref "JP18") (pin "1") (pinfunction "1_1") (pintype "passive"))
    )
    (net (code "13") (name "CSID5") (class "Default")
      (node (ref "CHIP_PRO") (pin "CSID5") (pinfunction "CSID5_CSID5") (pintype "bidirectional"))
      (node (ref "J4") (pin "3") (pinfunction "3_3") (pintype "passive"))
      (node (ref "JP19") (pin "1") (pinfunction "1_1") (pintype "passive"))
    )
    (net (code "14") (name "CSID6") (class "Default")
      (node (ref "CHIP_PRO") (pin "CSID6") (pinfunction "CSID6_CSID6") (pintype "bidirectional"))
      (node (ref "J4") (pin "2") (pinfunction "2_2") (pintype "passive"))
      (node (ref "JP20") (pin "1") (pinfunction "1_1") (pintype "passive"))
    )
    (net (code "15") (name "CSID7") (class "Default")
      (node (ref "CHIP_PRO") (pin "CSID7") (pinfunction "CSID7_CSID7") (pintype "bidirectional"))
      (node (ref "J4") (pin "1") (pinfunction "1_1") (pintype "passive"))
      (node (ref "JP21") (pin "1") (pinfunction "1_1") (pintype "passive"))
    )
    (net (code "16") (name "CSIHSYNC") (class "Default")
      (node (ref "CHIP_PRO") (pin "CSIHSYNC") (pinfunction "CSIHSYNC_CSIHSYNC") (pintype "bidirectional"))
      (node (ref "J4") (pin "10") (pinfunction "10_10") (pintype "passive"))
    )
    (net (code "17") (name "CSIMCLK") (class "Default")
      (node (ref "CHIP_PRO") (pin "CSIMCLK") (pinfunction "CSIMCLK_CSIMCLK") (pintype "bidirectional"))
      (node (ref "J4") (pin "11") (pinfunction "11_11") (pintype "passive"))
    )
    (net (code "18") (name "CSIPCK") (class "Default")
      (node (ref "CHIP_PRO") (pin "CSIPCK") (pinfunction "CSIPCK_CSIPCK") (pintype "bidirectional"))
      (node (ref "J4") (pin "12") (pinfunction "12_12") (pintype "passive"))
    )
    (net (code "19") (name "CSIVSYNC") (class "Default")
      (node (ref "CHIP_PRO") (pin "CSIVSYNC") (pinfunction "CSIVSYNC_CSIVSYNC") (pintype "bidirectional"))
      (node (ref "J4") (pin "9") (pinfunction "9_9") (pintype "passive"))
    )
    (net (code "20") (name "DM3_N") (class "Default")
      (node (ref "JP8") (pin "1") (pinfunction "1_1") (pintype "passive"))
      (node (ref "U2") (pin "8") (pinfunction "DM2_8") (pintype "bidirectional"))
    )
    (net (code "21") (name "DM3_P") (class "Default")
      (node (ref "JP9") (pin "1") (pinfunction "1_1") (pintype "passive"))
      (node (ref "U2") (pin "9") (pinfunction "DP2_9") (pintype "bidirectional"))
    )
    (net (code "22") (name "EXT_MIC") (class "Default")
      (node (ref "C15") (pin "1") (pinfunction "1_1") (pintype "passive"))
      (node (ref "JP11") (pin "1") (pinfunction "1_1") (pintype "passive"))
    )
    (net (code "23") (name "GND") (class "Default")
      (node (ref "+5V") (pin "C") (pinfunction "C_C") (pintype "passive"))
      (node (ref "3.3V") (pin "C") (pinfunction "C_C") (pintype "passive"))
      (node (ref "BAT") (pin "2") (pinfunction "1_2") (pintype "passive"))
      (node (ref "C10") (pin "2") (pinfunction "2_2") (pintype "passive"))
      (node (ref "C12") (pin "2") (pinfunction "2_2") (pintype "passive"))
      (node (ref "C13") (pin "2") (pinfunction "2_2") (pintype "passive"))
      (node (ref "C14") (pin "2") (pinfunction "2_2") (pintype "passive"))
      (node (ref "C17") (pin "2") (pinfunction "2_2") (pintype "passive"))
      (node (ref "C19") (pin "2") (pinfunction "2_2") (pintype "passive"))
      (node (ref "C2") (pin "2") (pinfunction "2_2") (pintype "passive"))
      (node (ref "C21") (pin "2") (pinfunction "2_2") (pintype "passive"))
      (node (ref "C22") (pin "2") (pinfunction "2_2") (pintype "passive"))
      (node (ref "C23") (pin "2") (pinfunction "2_2") (pintype "passive"))
      (node (ref "C25") (pin "2") (pinfunction "2_2") (pintype "passive"))
      (node (ref "C26") (pin "2") (pinfunction "2_2") (pintype "passive"))
      (node (ref "C30") (pin "2") (pinfunction "2_2") (pintype "passive"))
      (node (ref "CHIP_PRO") (pin "GND@0") (pinfunction "GND_GND@0") (pintype "power_in"))
      (node (ref "CHIP_PRO") (pin "GND@1") (pinfunction "GND_GND@1") (pintype "power_in"))
      (node (ref "CHIP_PRO") (pin "GND@2") (pinfunction "GND_GND@2") (pintype "power_in"))
      (node (ref "CHIP_PRO") (pin "GND@3") (pinfunction "GND_GND@3") (pintype "power_in"))
      (node (ref "CHIP_PRO") (pin "GND@4") (pinfunction "GND_GND@4") (pintype "power_in"))
      (node (ref "CHIP_PRO") (pin "GND@6") (pinfunction "GND_GND@6") (pintype "power_in"))
      (node (ref "CHIP_PRO") (pin "GND@7") (pinfunction "GND_GND@7") (pintype "power_in"))
      (node (ref "CN2") (pin "GND") (pinfunction "GND_GND") (pintype "bidirectional"))
      (node (ref "J1") (pin "GND") (pinfunction "GND_GND") (pintype "bidirectional"))
      (node (ref "J1") (pin "MT1") (pinfunction "GND_MT1") (pintype "bidirectional"))
      (node (ref "J1") (pin "MT2") (pinfunction "GND_MT2") (pintype "bidirectional"))
      (node (ref "J2") (pin "GND") (pinfunction "GND_GND") (pintype "bidirectional"))
      (node (ref "J3") (pin "1") (pinfunction "1_1") (pintype "passive"))
      (node (ref "J3") (pin "6") (pinfunction "6_6") (pintype "passive"))
      (node (ref "J4") (pin "16") (pinfunction "16_16") (pintype "passive"))
      (node (ref "J5") (pin "1") (pinfunction "1_1") (pintype "passive"))
      (node (ref "J6") (pin "3") (pinfunction "3_3") (pintype "passive"))
      (node (ref "J7") (pin "3") (pinfunction "3_3") (pintype "passive"))
      (node (ref "JP12") (pin "1") (pinfunction "1_1") (pintype "passive"))
      (node (ref "JP6") (pin "3") (pinfunction "3_3") (pintype "passive"))
      (node (ref "JP7") (pin "1") (pinfunction "1_1") (pintype "passive"))
      (node (ref "LED0") (pin "C") (pinfunction "C_C") (pintype "passive"))
      (node (ref "LED1") (pin "C") (pinfunction "C_C") (pintype "passive"))
      (node (ref "LED2") (pin "C") (pinfunction "C_C") (pintype "passive"))
      (node (ref "LED3") (pin "C") (pinfunction "C_C") (pintype "passive"))
      (node (ref "LED4") (pin "C") (pinfunction "C_C") (pintype "passive"))
      (node (ref "LED5") (pin "C") (pinfunction "C_C") (pintype "passive"))
      (node (ref "LED6") (pin "C") (pinfunction "C_C") (pintype "passive"))
      (node (ref "LED7") (pin "C") (pinfunction "C_C") (pintype "passive"))
      (node (ref "PWM1") (pin "C") (pinfunction "C_C") (pintype "passive"))
      (node (ref "PWM2") (pin "C") (pinfunction "C_C") (pintype "passive"))
      (node (ref "R14") (pin "1") (pinfunction "1_1") (pintype "passive"))
      (node (ref "R16") (pin "1") (pinfunction "1_1") (pintype "passive"))
      (node (ref "R2") (pin "1") (pinfunction "1_1") (pintype "passive"))
      (node (ref "R24") (pin "2") (pinfunction "2_2") (pintype "passive"))
      (node (ref "R34") (pin "2") (pinfunction "2_2") (pintype "passive"))
      (node (ref "R6") (pin "1") (pinfunction "1_1") (pintype "passive"))
      (node (ref "SW1") (pin "2") (pinfunction "2_2") (pintype "bidirectional"))
      (node (ref "U2") (pin "1") (pinfunction "VSS_1") (pintype "bidirectional"))
      (node (ref "U3") (pin "4") (pinfunction "GND_4") (pintype "bidirectional"))
      (node (ref "U3") (pin "PAD") (pinfunction "PAD_PAD") (pintype "bidirectional"))
      (node (ref "U5") (pin "2") (pinfunction "GND_2") (pintype "bidirectional"))
      (node (ref "UN0") (pin "13") (pinfunction "GND_13") (pintype "power_in"))
      (node (ref "UN0") (pin "5") (pinfunction "GND_5") (pintype "power_in"))
    )
    (net (code "24") (name "HPCOM") (class "Default")
      (node (ref "CHIP_PRO") (pin "HPCOM") (pinfunction "HPCOM_HPCOM") (pintype "bidirectional"))
      (node (ref "J5") (pin "3") (pinfunction "3_3") (pintype "passive"))
      (node (ref "JP6") (pin "1") (pinfunction "1_1") (pintype "passive"))
    )
    (net (code "25") (name "HPL") (class "Default")
      (node (ref "CHIP_PRO") (pin "HPL") (pinfunction "HPL_HPL") (pintype "bidirectional"))
      (node (ref "CN1") (pin "2") (pinfunction "L_2") (pintype "bidirectional"))
      (node (ref "J5") (pin "2") (pinfunction "2_2") (pintype "passive"))
    )
    (net (code "26") (name "HPR") (class "Default")
      (node (ref "CHIP_PRO") (pin "HPR") (pinfunction "HPR_HPR") (pintype "bidirectional"))
      (node (ref "CN1") (pin "3") (pinfunction "R_3") (pintype "bidirectional"))
      (node (ref "J5") (pin "4") (pinfunction "4_4") (pintype "passive"))
    )
    (net (code "27") (name "I2S+SPDIF") (class "Default")
      (node (ref "CHIP_PRO") (pin "I2S+SPDIF") (pinfunction "I2SSPDIF_I2S+SPDIF") (pintype "bidirectional"))
      (node (ref "J5") (pin "9") (pinfunction "9_9") (pintype "passive"))
    )
    (net (code "28") (name "I2S-BCLK") (class "Default")
      (node (ref "CHIP_PRO") (pin "I2S-BCLK") (pinfunction "I2SBCLK_I2S-BCLK") (pintype "bidirectional"))
      (node (ref "J5") (pin "6") (pinfunction "6_6") (pintype "passive"))
    )
    (net (code "29") (name "I2S-DO") (class "Default")
      (node (ref "CHIP_PRO") (pin "I2S-DO") (pinfunction "I2SDO_I2S-DO") (pintype "bidirectional"))
      (node (ref "J5") (pin "8") (pinfunction "8_8") (pintype "passive"))
    )
    (net (code "30") (name "I2S-LRCK") (class "Default")
      (node (ref "CHIP_PRO") (pin "I2S-LRCK") (pinfunction "I2SLRCK_I2S-LRCK") (pintype "bidirectional"))
      (node (ref "J5") (pin "7") (pinfunction "7_7") (pintype "passive"))
    )
    (net (code "31") (name "I2S-MCLK") (class "Default")
      (node (ref "CHIP_PRO") (pin "I2S-MCLK") (pinfunction "I2SMCLK_I2S-MCLK") (pintype "bidirectional"))
      (node (ref "J5") (pin "5") (pinfunction "5_5") (pintype "passive"))
    )
    (net (code "32") (name "IPSOUT") (class "Default")
      (node (ref "CHIP_PRO") (pin "IPSOUT") (pinfunction "IPSOUT_IPSOUT") (pintype "power_in"))
      (node (ref "J3") (pin "3") (pinfunction "3_3") (pintype "passive"))
    )
    (net (code "33") (name "LRADC") (class "Default")
      (node (ref "CHIP_PRO") (pin "LRADC") (pinfunction "LRADC_LRADC") (pintype "bidirectional"))
      (node (ref "J4") (pin "13") (pinfunction "13_13") (pintype "passive"))
    )
    (net (code "34") (name "MICGND1") (class "Default")
      (node (ref "C3") (pin "2") (pinfunction "2_2") (pintype "passive"))
      (node (ref "C6") (pin "2") (pinfunction "2_2") (pintype "passive"))
      (node (ref "JP12") (pin "2") (pinfunction "2_2") (pintype "passive"))
      (node (ref "MIC1") (pin "2") (pinfunction "GND_2") (pintype "bidirectional"))
      (node (ref "MIC1") (pin "3") (pinfunction "GND_3") (pintype "bidirectional"))
    )
    (net (code "35") (name "MICGND2") (class "Default")
      (node (ref "C4") (pin "2") (pinfunction "2_2") (pintype "passive"))
      (node (ref "C7") (pin "2") (pinfunction "2_2") (pintype "passive"))
      (node (ref "JP7") (pin "2") (pinfunction "2_2") (pintype "passive"))
      (node (ref "MIC2") (pin "2") (pinfunction "GND_2") (pintype "bidirectional"))
      (node (ref "MIC2") (pin "3") (pinfunction "GND_3") (pintype "bidirectional"))
    )
    (net (code "36") (name "MICIN1") (class "Default")
      (node (ref "CHIP_PRO") (pin "MICIN1") (pinfunction "MICIN1_MICIN1") (pintype "bidirectional"))
      (node (ref "J5") (pin "11") (pinfunction "11_11") (pintype "passive"))
      (node (ref "JP11") (pin "2") (pinfunction "2_2") (pintype "passive"))
    )
    (net (code "37") (name "MICIN2") (class "Default")
      (node (ref "CHIP_PRO") (pin "MICIN2") (pinfunction "MICIN2_MICIN2") (pintype "bidirectional"))
      (node (ref "J5") (pin "12") (pinfunction "12_12") (pintype "passive"))
      (node (ref "JP3") (pin "2") (pinfunction "2_2") (pintype "passive"))
    )
    (net (code "38") (name "Net-(+5V-PadA)") (class "Default")
      (node (ref "+5V") (pin "A") (pinfunction "A_A") (pintype "passive"))
      (node (ref "R7") (pin "2") (pinfunction "2_2") (pintype "passive"))
    )
    (net (code "39") (name "Net-(3.3V-PadA)") (class "Default")
      (node (ref "3.3V") (pin "A") (pinfunction "A_A") (pintype "passive"))
      (node (ref "R1") (pin "2") (pinfunction "2_2") (pintype "passive"))
    )
    (net (code "40") (name "Net-(C2-Pad1)") (class "Default")
      (node (ref "C2") (pin "1") (pinfunction "1_1") (pintype "passive"))
      (node (ref "R22") (pin "1") (pinfunction "1_1") (pintype "passive"))
      (node (ref "R23") (pin "1") (pinfunction "1_1") (pintype "passive"))
    )
    (net (code "41") (name "Net-(C8-Pad2)") (class "Default")
      (node (ref "C8") (pin "2") (pinfunction "2_2") (pintype "passive"))
      (node (ref "JP11") (pin "3") (pinfunction "3_3") (pintype "passive"))
    )
    (net (code "42") (name "Net-(C9-Pad2)") (class "Default")
      (node (ref "C9") (pin "2") (pinfunction "2_2") (pintype "passive"))
      (node (ref "JP3") (pin "1") (pinfunction "1_1") (pintype "passive"))
    )
    (net (code "43") (name "Net-(C20-Pad2)") (class "Default")
      (node (ref "C20") (pin "2") (pinfunction "2_2") (pintype "passive"))
      (node (ref "R14") (pin "2") (pinfunction "2_2") (pintype "passive"))
    )
    (net (code "44") (name "Net-(CN1-GND)") (class "Default")
      (node (ref "CN1") (pin "4") (pinfunction "GND_4") (pintype "bidirectional"))
      (node (ref "JP6") (pin "2") (pinfunction "2_2") (pintype "passive"))
    )
    (net (code "45") (name "Net-(CN1-MIC)") (class "Default")
      (node (ref "C1") (pin "1") (pinfunction "1_1") (pintype "passive"))
      (node (ref "C15") (pin "2") (pinfunction "2_2") (pintype "passive"))
      (node (ref "CN1") (pin "1") (pinfunction "MIC_1") (pintype "bidirectional"))
      (node (ref "R22") (pin "2") (pinfunction "2_2") (pintype "passive"))
    )
    (net (code "46") (name "Net-(L3-1)") (class "Default")
      (node (ref "C24") (pin "2") (pinfunction "2_2") (pintype "passive"))
      (node (ref "L3") (pin "P$1") (pinfunction "1_P$1") (pintype "passive"))
      (node (ref "U3") (pin "3") (pinfunction "SW_3") (pintype "bidirectional"))
    )
    (net (code "47") (name "Net-(LED0-PadA)") (class "Default")
      (node (ref "LED0") (pin "A") (pinfunction "A_A") (pintype "passive"))
      (node (ref "R26") (pin "2") (pinfunction "2_2") (pintype "passive"))
    )
    (net (code "48") (name "Net-(LED1-PadA)") (class "Default")
      (node (ref "LED1") (pin "A") (pinfunction "A_A") (pintype "passive"))
      (node (ref "R27") (pin "2") (pinfunction "2_2") (pintype "passive"))
    )
    (net (code "49") (name "Net-(LED2-PadA)") (class "Default")
      (node (ref "LED2") (pin "A") (pinfunction "A_A") (pintype "passive"))
      (node (ref "R28") (pin "2") (pinfunction "2_2") (pintype "passive"))
    )
    (net (code "50") (name "Net-(LED3-PadA)") (class "Default")
      (node (ref "LED3") (pin "A") (pinfunction "A_A") (pintype "passive"))
      (node (ref "R29") (pin "2") (pinfunction "2_2") (pintype "passive"))
    )
    (net (code "51") (name "Net-(LED4-PadA)") (class "Default")
      (node (ref "LED4") (pin "A") (pinfunction "A_A") (pintype "passive"))
      (node (ref "R30") (pin "2") (pinfunction "2_2") (pintype "passive"))
    )
    (net (code "52") (name "Net-(LED5-PadA)") (class "Default")
      (node (ref "LED5") (pin "A") (pinfunction "A_A") (pintype "passive"))
      (node (ref "R31") (pin "2") (pinfunction "2_2") (pintype "passive"))
    )
    (net (code "53") (name "Net-(LED6-PadA)") (class "Default")
      (node (ref "LED6") (pin "A") (pinfunction "A_A") (pintype "passive"))
      (node (ref "R32") (pin "2") (pinfunction "2_2") (pintype "passive"))
    )
    (net (code "54") (name "Net-(LED7-PadA)") (class "Default")
      (node (ref "LED7") (pin "A") (pinfunction "A_A") (pintype "passive"))
      (node (ref "R33") (pin "2") (pinfunction "2_2") (pintype "passive"))
    )
    (net (code "55") (name "Net-(MIC1-OUT)") (class "Default")
      (node (ref "C6") (pin "1") (pinfunction "1_1") (pintype "passive"))
      (node (ref "C8") (pin "1") (pinfunction "1_1") (pintype "passive"))
      (node (ref "MIC1") (pin "4") (pinfunction "OUT_4") (pintype "bidirectional"))
    )
    (net (code "56") (name "Net-(MIC1-VDD)") (class "Default")
      (node (ref "C3") (pin "1") (pinfunction "1_1") (pintype "passive"))
      (node (ref "JP13") (pin "2") (pinfunction "2_2") (pintype "passive"))
      (node (ref "MIC1") (pin "1") (pinfunction "VDD_1") (pintype "bidirectional"))
    )
    (net (code "57") (name "Net-(MIC2-OUT)") (class "Default")
      (node (ref "C7") (pin "1") (pinfunction "1_1") (pintype "passive"))
      (node (ref "C9") (pin "1") (pinfunction "1_1") (pintype "passive"))
      (node (ref "MIC2") (pin "4") (pinfunction "OUT_4") (pintype "bidirectional"))
    )
    (net (code "58") (name "Net-(MIC2-VDD)") (class "Default")
      (node (ref "C4") (pin "1") (pinfunction "1_1") (pintype "passive"))
      (node (ref "JP22") (pin "2") (pinfunction "2_2") (pintype "passive"))
      (node (ref "MIC2") (pin "1") (pinfunction "VDD_1") (pintype "bidirectional"))
    )
    (net (code "59") (name "Net-(PWM1-PadA)") (class "Default")
      (node (ref "PWM1") (pin "A") (pinfunction "A_A") (pintype "passive"))
      (node (ref "R3") (pin "2") (pinfunction "2_2") (pintype "passive"))
    )
    (net (code "60") (name "Net-(PWM2-PadA)") (class "Default")
      (node (ref "PWM2") (pin "A") (pinfunction "A_A") (pintype "passive"))
      (node (ref "R4") (pin "2") (pinfunction "2_2") (pintype "passive"))
    )
    (net (code "61") (name "Net-(PWR-PadC)") (class "Default")
      (node (ref "PWR") (pin "C") (pinfunction "C_C") (pintype "passive"))
      (node (ref "R2") (pin "2") (pinfunction "2_2") (pintype "passive"))
    )
    (net (code "62") (name "Net-(Q1-B)") (class "Default")
      (node (ref "JP1") (pin "2") (pinfunction "2_2") (pintype "passive"))
      (node (ref "Q1") (pin "1") (pinfunction "B_1") (pintype "passive"))
    )
    (net (code "63") (name "Net-(Q1-E)") (class "Default")
      (node (ref "Q1") (pin "2") (pinfunction "E_2") (pintype "passive"))
      (node (ref "R3") (pin "1") (pinfunction "1_1") (pintype "passive"))
    )
    (net (code "64") (name "Net-(Q2-B)") (class "Default")
      (node (ref "JP2") (pin "2") (pinfunction "2_2") (pintype "passive"))
      (node (ref "Q2") (pin "1") (pinfunction "B_1") (pintype "passive"))
    )
    (net (code "65") (name "Net-(Q2-E)") (class "Default")
      (node (ref "Q2") (pin "2") (pinfunction "E_2") (pintype "passive"))
      (node (ref "R4") (pin "1") (pinfunction "1_1") (pintype "passive"))
    )
    (net (code "66") (name "Net-(Q3-B)") (class "Default")
      (node (ref "JP14") (pin "2") (pinfunction "2_2") (pintype "passive"))
      (node (ref "Q3") (pin "1") (pinfunction "B_1") (pintype "passive"))
    )
    (net (code "67") (name "Net-(Q3-E)") (class "Default")
      (node (ref "Q3") (pin "2") (pinfunction "E_2") (pintype "passive"))
      (node (ref "R26") (pin "1") (pinfunction "1_1") (pintype "passive"))
    )
    (net (code "68") (name "Net-(Q4-B)") (class "Default")
      (node (ref "JP15") (pin "2") (pinfunction "2_2") (pintype "passive"))
      (node (ref "Q4") (pin "1") (pinfunction "B_1") (pintype "passive"))
    )
    (net (code "69") (name "Net-(Q4-E)") (class "Default")
      (node (ref "Q4") (pin "2") (pinfunction "E_2") (pintype "passive"))
      (node (ref "R27") (pin "1") (pinfunction "1_1") (pintype "passive"))
    )
    (net (code "70") (name "Net-(Q5-B)") (class "Default")
      (node (ref "JP16") (pin "2") (pinfunction "2_2") (pintype "passive"))
      (node (ref "Q5") (pin "1") (pinfunction "B_1") (pintype "passive"))
    )
    (net (code "71") (name "Net-(Q5-E)") (class "Default")
      (node (ref "Q5") (pin "2") (pinfunction "E_2") (pintype "passive"))
      (node (ref "R28") (pin "1") (pinfunction "1_1") (pintype "passive"))
    )
    (net (code "72") (name "Net-(Q6-B)") (class "Default")
      (node (ref "JP17") (pin "2") (pinfunction "2_2") (pintype "passive"))
      (node (ref "Q6") (pin "1") (pinfunction "B_1") (pintype "passive"))
    )
    (net (code "73") (name "Net-(Q6-E)") (class "Default")
      (node (ref "Q6") (pin "2") (pinfunction "E_2") (pintype "passive"))
      (node (ref "R29") (pin "1") (pinfunction "1_1") (pintype "passive"))
    )
    (net (code "74") (name "Net-(Q7-B)") (class "Default")
      (node (ref "JP18") (pin "2") (pinfunction "2_2") (pintype "passive"))
      (node (ref "Q7") (pin "1") (pinfunction "B_1") (pintype "passive"))
    )
    (net (code "75") (name "Net-(Q7-E)") (class "Default")
      (node (ref "Q7") (pin "2") (pinfunction "E_2") (pintype "passive"))
      (node (ref "R30") (pin "1") (pinfunction "1_1") (pintype "passive"))
    )
    (net (code "76") (name "Net-(Q8-B)") (class "Default")
      (node (ref "JP19") (pin "2") (pinfunction "2_2") (pintype "passive"))
      (node (ref "Q8") (pin "1") (pinfunction "B_1") (pintype "passive"))
    )
    (net (code "77") (name "Net-(Q8-E)") (class "Default")
      (node (ref "Q8") (pin "2") (pinfunction "E_2") (pintype "passive"))
      (node (ref "R31") (pin "1") (pinfunction "1_1") (pintype "passive"))
    )
    (net (code "78") (name "Net-(Q9-B)") (class "Default")
      (node (ref "JP20") (pin "2") (pinfunction "2_2") (pintype "passive"))
      (node (ref "Q9") (pin "1") (pinfunction "B_1") (pintype "passive"))
    )
    (net (code "79") (name "Net-(Q9-E)") (class "Default")
      (node (ref "Q9") (pin "2") (pinfunction "E_2") (pintype "passive"))
      (node (ref "R32") (pin "1") (pinfunction "1_1") (pintype "passive"))
    )
    (net (code "80") (name "Net-(Q10-B)") (class "Default")
      (node (ref "JP21") (pin "2") (pinfunction "2_2") (pintype "passive"))
      (node (ref "Q10") (pin "1") (pinfunction "B_1") (pintype "passive"))
    )
    (net (code "81") (name "Net-(Q10-E)") (class "Default")
      (node (ref "Q10") (pin "2") (pinfunction "E_2") (pintype "passive"))
      (node (ref "R33") (pin "1") (pinfunction "1_1") (pintype "passive"))
    )
    (net (code "82") (name "Net-(R12-Pad2)") (class "Default")
      (node (ref "R12") (pin "2") (pinfunction "2_2") (pintype "passive"))
      (node (ref "RX_LED") (pin "A") (pinfunction "A_A") (pintype "passive"))
    )
    (net (code "83") (name "Net-(R13-Pad2)") (class "Default")
      (node (ref "R13") (pin "2") (pinfunction "2_2") (pintype "passive"))
      (node (ref "TX_LED") (pin "A") (pinfunction "A_A") (pintype "passive"))
    )
    (net (code "84") (name "Net-(U2-BUSJ)") (class "Default")
      (node (ref "R9") (pin "2") (pinfunction "2_2") (pintype "passive"))
      (node (ref "U2") (pin "19") (pinfunction "BUSJ_19") (pintype "bidirectional"))
    )
    (net (code "85") (name "Net-(U2-REXT)") (class "Default")
      (node (ref "R34") (pin "1") (pinfunction "1_1") (pintype "passive"))
      (node (ref "U2") (pin "14") (pinfunction "REXT_14") (pintype "bidirectional"))
    )
    (net (code "86") (name "Net-(U2-XIN)") (class "Default")
      (node (ref "U2") (pin "3") (pinfunction "XIN_3") (pintype "bidirectional"))
      (node (ref "X1") (pin "3") (pinfunction "XTALOUT_3") (pintype "bidirectional"))
    )
    (net (code "87") (name "Net-(U2-XOUT)") (class "Default")
      (node (ref "U2") (pin "2") (pinfunction "XOUT_2") (pintype "bidirectional"))
      (node (ref "X1") (pin "1") (pinfunction "XTALIN_1") (pintype "bidirectional"))
    )
    (net (code "88") (name "Net-(U2-XRSTJ)") (class "Default")
      (node (ref "R10") (pin "2") (pinfunction "2_2") (pintype "passive"))
      (node (ref "U2") (pin "17") (pinfunction "XRSTJ_17") (pintype "bidirectional"))
    )
    (net (code "89") (name "Net-(U3-BS)") (class "Default")
      (node (ref "C24") (pin "1") (pinfunction "1_1") (pintype "passive"))
      (node (ref "U3") (pin "1") (pinfunction "BS_1") (pintype "bidirectional"))
    )
    (net (code "90") (name "Net-(U3-COMP)") (class "Default")
      (node (ref "C20") (pin "1") (pinfunction "1_1") (pintype "passive"))
      (node (ref "U3") (pin "6") (pinfunction "COMP_6") (pintype "bidirectional"))
    )
    (net (code "91") (name "Net-(U3-EN)") (class "Default")
      (node (ref "R15") (pin "1") (pinfunction "1_1") (pintype "passive"))
      (node (ref "U3") (pin "7") (pinfunction "EN_7") (pintype "bidirectional"))
    )
    (net (code "92") (name "Net-(U3-FB)") (class "Default")
      (node (ref "R16") (pin "2") (pinfunction "2_2") (pintype "passive"))
      (node (ref "R17") (pin "2") (pinfunction "2_2") (pintype "passive"))
      (node (ref "U3") (pin "5") (pinfunction "FB_5") (pintype "bidirectional"))
    )
    (net (code "93") (name "Net-(U3-SS)") (class "Default")
      (node (ref "C23") (pin "1") (pinfunction "1_1") (pintype "passive"))
      (node (ref "U3") (pin "8") (pinfunction "SS_8") (pintype "bidirectional"))
    )
    (net (code "94") (name "Net-(U5-EN)") (class "Default")
      (node (ref "R25") (pin "2") (pinfunction "2_2") (pintype "passive"))
      (node (ref "U5") (pin "3") (pinfunction "EN_3") (pintype "bidirectional"))
    )
    (net (code "95") (name "Net-(U5-ILIM)") (class "Default")
      (node (ref "R24") (pin "1") (pinfunction "1_1") (pintype "passive"))
      (node (ref "U5") (pin "5") (pinfunction "ILIM_5") (pintype "bidirectional"))
    )
    (net (code "96") (name "Net-(U5-VIN)") (class "Default")
      (node (ref "JP24") (pin "2") (pinfunction "2_2") (pintype "passive"))
      (node (ref "U5") (pin "1") (pinfunction "VIN_1") (pintype "bidirectional"))
    )
    (net (code "97") (name "Net-(U5-VOUT)") (class "Default")
      (node (ref "J2") (pin "VBUS") (pinfunction "VBUS_VBUS") (pintype "bidirectional"))
      (node (ref "U5") (pin "6") (pinfunction "VOUT_6") (pintype "bidirectional"))
    )
    (net (code "98") (name "Net-(UN0-CBUS3)") (class "Default")
      (node (ref "R6") (pin "2") (pinfunction "2_2") (pintype "passive"))
      (node (ref "UN0") (pin "16") (pinfunction "CBUS3_16") (pintype "bidirectional"))
    )
    (net (code "99") (name "PWM0") (class "Default")
      (node (ref "CHIP_PRO") (pin "PWM0") (pinfunction "PWM0_PWM0") (pintype "bidirectional"))
      (node (ref "J3") (pin "9") (pinfunction "9_9") (pintype "passive"))
      (node (ref "J6") (pin "1") (pinfunction "1_1") (pintype "passive"))
      (node (ref "JP1") (pin "1") (pinfunction "1_1") (pintype "passive"))
    )
    (net (code "100") (name "PWM1") (class "Default")
      (node (ref "CHIP_PRO") (pin "PWM1") (pinfunction "PWM1_PWM1") (pintype "bidirectional"))
      (node (ref "J3") (pin "10") (pinfunction "10_10") (pintype "passive"))
      (node (ref "J7") (pin "1") (pinfunction "1_1") (pintype "passive"))
      (node (ref "JP2") (pin "1") (pinfunction "1_1") (pintype "passive"))
    )
    (net (code "101") (name "PWRON") (class "Default")
      (node (ref "CHIP_PRO") (pin "PWRON") (pinfunction "PWRON_PWRON") (pintype "bidirectional"))
      (node (ref "J3") (pin "5") (pinfunction "5_5") (pintype "passive"))
      (node (ref "SW1") (pin "1") (pinfunction "1_1") (pintype "bidirectional"))
    )
    (net (code "102") (name "RXD") (class "Default")
      (node (ref "JP5") (pin "1") (pinfunction "1_1") (pintype "passive"))
      (node (ref "UN0") (pin "4") (pinfunction "RXD_4") (pintype "input"))
    )
    (net (code "103") (name "RXLED") (class "Default")
      (node (ref "RX_LED") (pin "C") (pinfunction "C_C") (pintype "passive"))
      (node (ref "UN0") (pin "7") (pinfunction "CBUS2_7") (pintype "bidirectional"))
    )
    (net (code "104") (name "TS") (class "Default")
      (node (ref "CHIP_PRO") (pin "TS") (pinfunction "TS_TS") (pintype "bidirectional"))
      (node (ref "J3") (pin "7") (pinfunction "7_7") (pintype "passive"))
    )
    (net (code "105") (name "TWI1-SCK") (class "Default")
      (node (ref "CHIP_PRO") (pin "TWI1-SDA") (pinfunction "TWI1-SDA_TWI1-SDA") (pintype "bidirectional"))
      (node (ref "J3") (pin "11") (pinfunction "11_11") (pintype "passive"))
    )
    (net (code "106") (name "TWI1-SDA") (class "Default")
      (node (ref "CHIP_PRO") (pin "TWI1-SCK") (pinfunction "TWI1-SCK_TWI1-SCK") (pintype "bidirectional"))
      (node (ref "J3") (pin "12") (pinfunction "12_12") (pintype "passive"))
    )
    (net (code "107") (name "TXD") (class "Default")
      (node (ref "JP4") (pin "1") (pinfunction "1_1") (pintype "passive"))
      (node (ref "UN0") (pin "1") (pinfunction "TXD_1") (pintype "output"))
    )
    (net (code "108") (name "TXLED") (class "Default")
      (node (ref "TX_LED") (pin "C") (pinfunction "C_C") (pintype "passive"))
      (node (ref "UN0") (pin "14") (pinfunction "CBUS1_14") (pintype "bidirectional"))
    )
    (net (code "109") (name "UART1-RX") (class "Default")
      (node (ref "CHIP_PRO") (pin "UART1-RX") (pinfunction "UART1-RX_UART1-RX") (pintype "bidirectional"))
      (node (ref "J4") (pin "14") (pinfunction "14_14") (pintype "passive"))
      (node (ref "JP4") (pin "2") (pinfunction "2_2") (pintype "passive"))
    )
    (net (code "110") (name "UART1-TX") (class "Default")
      (node (ref "CHIP_PRO") (pin "UART1-TX") (pinfunction "UART1-TX_UART1-TX") (pintype "bidirectional"))
      (node (ref "J4") (pin "15") (pinfunction "15_15") (pintype "passive"))
      (node (ref "JP5") (pin "2") (pinfunction "2_2") (pintype "passive"))
    )
    (net (code "111") (name "UART2-CTS") (class "Default")
      (node (ref "CHIP_PRO") (pin "UART2-CTS") (pinfunction "UART2-CTS_UART2-CTS") (pintype "bidirectional"))
      (node (ref "J3") (pin "15") (pinfunction "15_15") (pintype "passive"))
    )
    (net (code "112") (name "UART2-RTS") (class "Default")
      (node (ref "CHIP_PRO") (pin "UART2-RTS") (pinfunction "UART2-RTS_UART2-RTS") (pintype "bidirectional"))
      (node (ref "J3") (pin "16") (pinfunction "16_16") (pintype "passive"))
    )
    (net (code "113") (name "UART2-RX") (class "Default")
      (node (ref "CHIP_PRO") (pin "UART2-RX") (pinfunction "UART2-RX_UART2-RX") (pintype "bidirectional"))
      (node (ref "J3") (pin "14") (pinfunction "14_14") (pintype "passive"))
    )
    (net (code "114") (name "UART2-TX") (class "Default")
      (node (ref "CHIP_PRO") (pin "UART2-TX") (pinfunction "UART2-TX_UART2-TX") (pintype "bidirectional"))
      (node (ref "J3") (pin "13") (pinfunction "13_13") (pintype "passive"))
    )
    (net (code "115") (name "USB0_N") (class "Default")
      (node (ref "CHIP_PRO") (pin "USB0_N") (pinfunction "USB0_N_USB0_N") (pintype "bidirectional"))
      (node (ref "JP8") (pin "2") (pinfunction "2_2") (pintype "passive"))
    )
    (net (code "116") (name "USB0_P") (class "Default")
      (node (ref "CHIP_PRO") (pin "USB0_P") (pinfunction "USB0_P_USB0_P") (pintype "bidirectional"))
      (node (ref "JP9") (pin "2") (pinfunction "2_2") (pintype "passive"))
    )
    (net (code "117") (name "USB1_N") (class "Default")
      (node (ref "CHIP_PRO") (pin "USB1_N") (pinfunction "USB1_N_USB1_N") (pintype "bidirectional"))
      (node (ref "J2") (pin "D-") (pinfunction "D-_D-") (pintype "bidirectional"))
    )
    (net (code "118") (name "USB1_P") (class "Default")
      (node (ref "CHIP_PRO") (pin "USB1_P") (pinfunction "USB1_P_USB1_P") (pintype "bidirectional"))
      (node (ref "J2") (pin "D+") (pinfunction "D+_D+") (pintype "bidirectional"))
    )
    (net (code "119") (name "USBDBG_N") (class "Default")
      (node (ref "J1") (pin "D-") (pinfunction "D-_D-") (pintype "bidirectional"))
      (node (ref "U2") (pin "15") (pinfunction "DMU_15") (pintype "bidirectional"))
    )
    (net (code "120") (name "USBDBG_P") (class "Default")
      (node (ref "J1") (pin "D+") (pinfunction "D+_D+") (pintype "bidirectional"))
      (node (ref "U2") (pin "16") (pinfunction "DPU_16") (pintype "bidirectional"))
    )
    (net (code "121") (name "USBUART_N") (class "Default")
      (node (ref "U2") (pin "4") (pinfunction "DM4_4") (pintype "bidirectional"))
      (node (ref "UN0") (pin "9") (pinfunction "USBDM_9") (pintype "bidirectional"))
    )
    (net (code "122") (name "USBUART_P") (class "Default")
      (node (ref "U2") (pin "5") (pinfunction "DP4_5") (pintype "bidirectional"))
      (node (ref "UN0") (pin "8") (pinfunction "USBDP_8") (pintype "bidirectional"))
    )
    (net (code "123") (name "VCCIO") (class "Default")
      (node (ref "C10") (pin "1") (pinfunction "1_1") (pintype "passive"))
      (node (ref "UN0") (pin "10") (pinfunction "3V3OUT_10") (pintype "output"))
      (node (ref "UN0") (pin "11") (pinfunction "~{RESET}_11") (pintype "input"))
      (node (ref "UN0") (pin "3") (pinfunction "VCCIO_3") (pintype "power_in"))
    )
    (net (code "124") (name "VDD") (class "Default")
      (node (ref "CHIP_PRO") (pin "VCC3V3") (pinfunction "VCC3V3_VCC3V3") (pintype "power_in"))
      (node (ref "J3") (pin "2") (pinfunction "2_2") (pintype "passive"))
      (node (ref "JP13") (pin "1") (pinfunction "1_1") (pintype "passive"))
      (node (ref "JP22") (pin "1") (pinfunction "1_1") (pintype "passive"))
      (node (ref "Q1") (pin "3") (pinfunction "C_3") (pintype "passive"))
      (node (ref "Q10") (pin "3") (pinfunction "C_3") (pintype "passive"))
      (node (ref "Q2") (pin "3") (pinfunction "C_3") (pintype "passive"))
      (node (ref "Q3") (pin "3") (pinfunction "C_3") (pintype "passive"))
      (node (ref "Q4") (pin "3") (pinfunction "C_3") (pintype "passive"))
      (node (ref "Q5") (pin "3") (pinfunction "C_3") (pintype "passive"))
      (node (ref "Q6") (pin "3") (pinfunction "C_3") (pintype "passive"))
      (node (ref "Q7") (pin "3") (pinfunction "C_3") (pintype "passive"))
      (node (ref "Q8") (pin "3") (pinfunction "C_3") (pintype "passive"))
      (node (ref "Q9") (pin "3") (pinfunction "C_3") (pintype "passive"))
      (node (ref "R1") (pin "1") (pinfunction "1_1") (pintype "passive"))
      (node (ref "R12") (pin "1") (pinfunction "1_1") (pintype "passive"))
      (node (ref "R13") (pin "1") (pinfunction "1_1") (pintype "passive"))
      (node (ref "R25") (pin "1") (pinfunction "1_1") (pintype "passive"))
    )
    (net (code "125") (name "VIN") (class "Default")
      (node (ref "C21") (pin "1") (pinfunction "1_1") (pintype "passive"))
      (node (ref "C22") (pin "1") (pinfunction "1_1") (pintype "passive"))
      (node (ref "CN2") (pin "PWR") (pinfunction "PWR_PWR") (pintype "bidirectional"))
      (node (ref "R15") (pin "2") (pinfunction "2_2") (pintype "passive"))
      (node (ref "U3") (pin "2") (pinfunction "IN_2") (pintype "bidirectional"))
    )
    (net (code "126") (name "VMIC") (class "Default")
      (node (ref "CHIP_PRO") (pin "VMIC") (pinfunction "VMIC_VMIC") (pintype "bidirectional"))
      (node (ref "J5") (pin "13") (pinfunction "13_13") (pintype "passive"))
      (node (ref "JP13") (pin "3") (pinfunction "3_3") (pintype "passive"))
      (node (ref "JP22") (pin "3") (pinfunction "3_3") (pintype "passive"))
      (node (ref "R23") (pin "2") (pinfunction "2_2") (pintype "passive"))
    )
    (net (code "127") (name "VUSB") (class "Default")
      (node (ref "CHIP_PRO") (pin "VBUS") (pinfunction "VBUS_VBUS") (pintype "power_in"))
      (node (ref "JP10") (pin "2") (pinfunction "2_2") (pintype "passive"))
    )
    (net (code "128") (name "VUSB1") (class "Default")
      (node (ref "C12") (pin "1") (pinfunction "1_1") (pintype "passive"))
      (node (ref "C17") (pin "1") (pinfunction "1_1") (pintype "passive"))
      (node (ref "J1") (pin "VBUS") (pinfunction "VBUS_VBUS") (pintype "bidirectional"))
      (node (ref "JP10") (pin "1") (pinfunction "1_1") (pintype "passive"))
      (node (ref "JP24") (pin "3") (pinfunction "3_3") (pintype "passive"))
      (node (ref "PWR") (pin "A") (pinfunction "A_A") (pintype "passive"))
      (node (ref "U2") (pin "20") (pinfunction "VDD5_20") (pintype "bidirectional"))
      (node (ref "UN0") (pin "12") (pinfunction "VCC_12") (pintype "power_in"))
    )
    (net (code "129") (name "unconnected-(CN2-PadGNDBREAK)") (class "Default")
      (node (ref "CN2") (pin "GNDBREAK") (pinfunction "GNDBREAK_GNDBREAK") (pintype "bidirectional"))
    )
    (net (code "130") (name "unconnected-(SW2-PadSW1)") (class "Default")
      (node (ref "SW2") (pin "SW1") (pinfunction "SW1_SW1") (pintype "bidirectional"))
    )
    (net (code "131") (name "unconnected-(SW3-PadSW1)") (class "Default")
      (node (ref "SW3") (pin "SW1") (pinfunction "SW1_SW1") (pintype "bidirectional"))
    )
    (net (code "132") (name "unconnected-(U2-DM1-Pad10)") (class "Default")
      (node (ref "U2") (pin "10") (pinfunction "DM1_10") (pintype "bidirectional"))
    )
    (net (code "133") (name "unconnected-(U2-DM3-Pad6)") (class "Default")
      (node (ref "U2") (pin "6") (pinfunction "DM3_6") (pintype "bidirectional"))
    )
    (net (code "134") (name "unconnected-(U2-DP1-Pad11)") (class "Default")
      (node (ref "U2") (pin "11") (pinfunction "DP1_11") (pintype "bidirectional"))
    )
    (net (code "135") (name "unconnected-(U2-DP3-Pad7)") (class "Default")
      (node (ref "U2") (pin "7") (pinfunction "DP3_7") (pintype "bidirectional"))
    )
    (net (code "136") (name "unconnected-(U2-DRV-Pad22)") (class "Default")
      (node (ref "U2") (pin "22") (pinfunction "DRV_22") (pintype "bidirectional"))
    )
    (net (code "137") (name "unconnected-(U2-LED1-Pad23)") (class "Default")
      (node (ref "U2") (pin "23") (pinfunction "LED1_23") (pintype "bidirectional"))
    )
    (net (code "138") (name "unconnected-(U2-LED2-Pad24)") (class "Default")
      (node (ref "U2") (pin "24") (pinfunction "LED2_24") (pintype "bidirectional"))
    )
    (net (code "139") (name "unconnected-(U2-PWRJ-Pad25)") (class "Default")
      (node (ref "U2") (pin "25") (pinfunction "PWRJ_25") (pintype "bidirectional"))
    )
    (net (code "140") (name "unconnected-(U2-TESTJ-Pad27)") (class "Default")
      (node (ref "U2") (pin "27") (pinfunction "TESTJ_27") (pintype "bidirectional"))
    )
    (net (code "141") (name "unconnected-(U5-FAULT-Pad4)") (class "Default")
      (node (ref "U5") (pin "4") (pinfunction "FAULT_4") (pintype "bidirectional"))
    )
    (net (code "142") (name "unconnected-(UN0-CBUS0-Pad15)") (class "Default")
      (node (ref "UN0") (pin "15") (pinfunction "CBUS0_15") (pintype "bidirectional"))
    )
    (net (code "143") (name "unconnected-(UN0-~{CTS}-Pad6)") (class "Default")
      (node (ref "UN0") (pin "6") (pinfunction "~{CTS}_6") (pintype "input"))
    )
    (net (code "144") (name "unconnected-(UN0-~{RTS}-Pad2)") (class "Default")
      (node (ref "UN0") (pin "2") (pinfunction "~{RTS}_2") (pintype "output"))
    )
    (net (code "145") (name "unconnected-(X1-GND_2-Pad2)") (class "Default")
      (node (ref "X1") (pin "2") (pinfunction "GND_2_2") (pintype "bidirectional"))
    )
    (net (code "146") (name "unconnected-(X1-GND_4-Pad4)") (class "Default")
      (node (ref "X1") (pin "4") (pinfunction "GND_4_4") (pintype "bidirectional"))
    )
  )
)
